# ImageProc_2_5.net
KiCad netlist of a schematic drawn in EAGLE
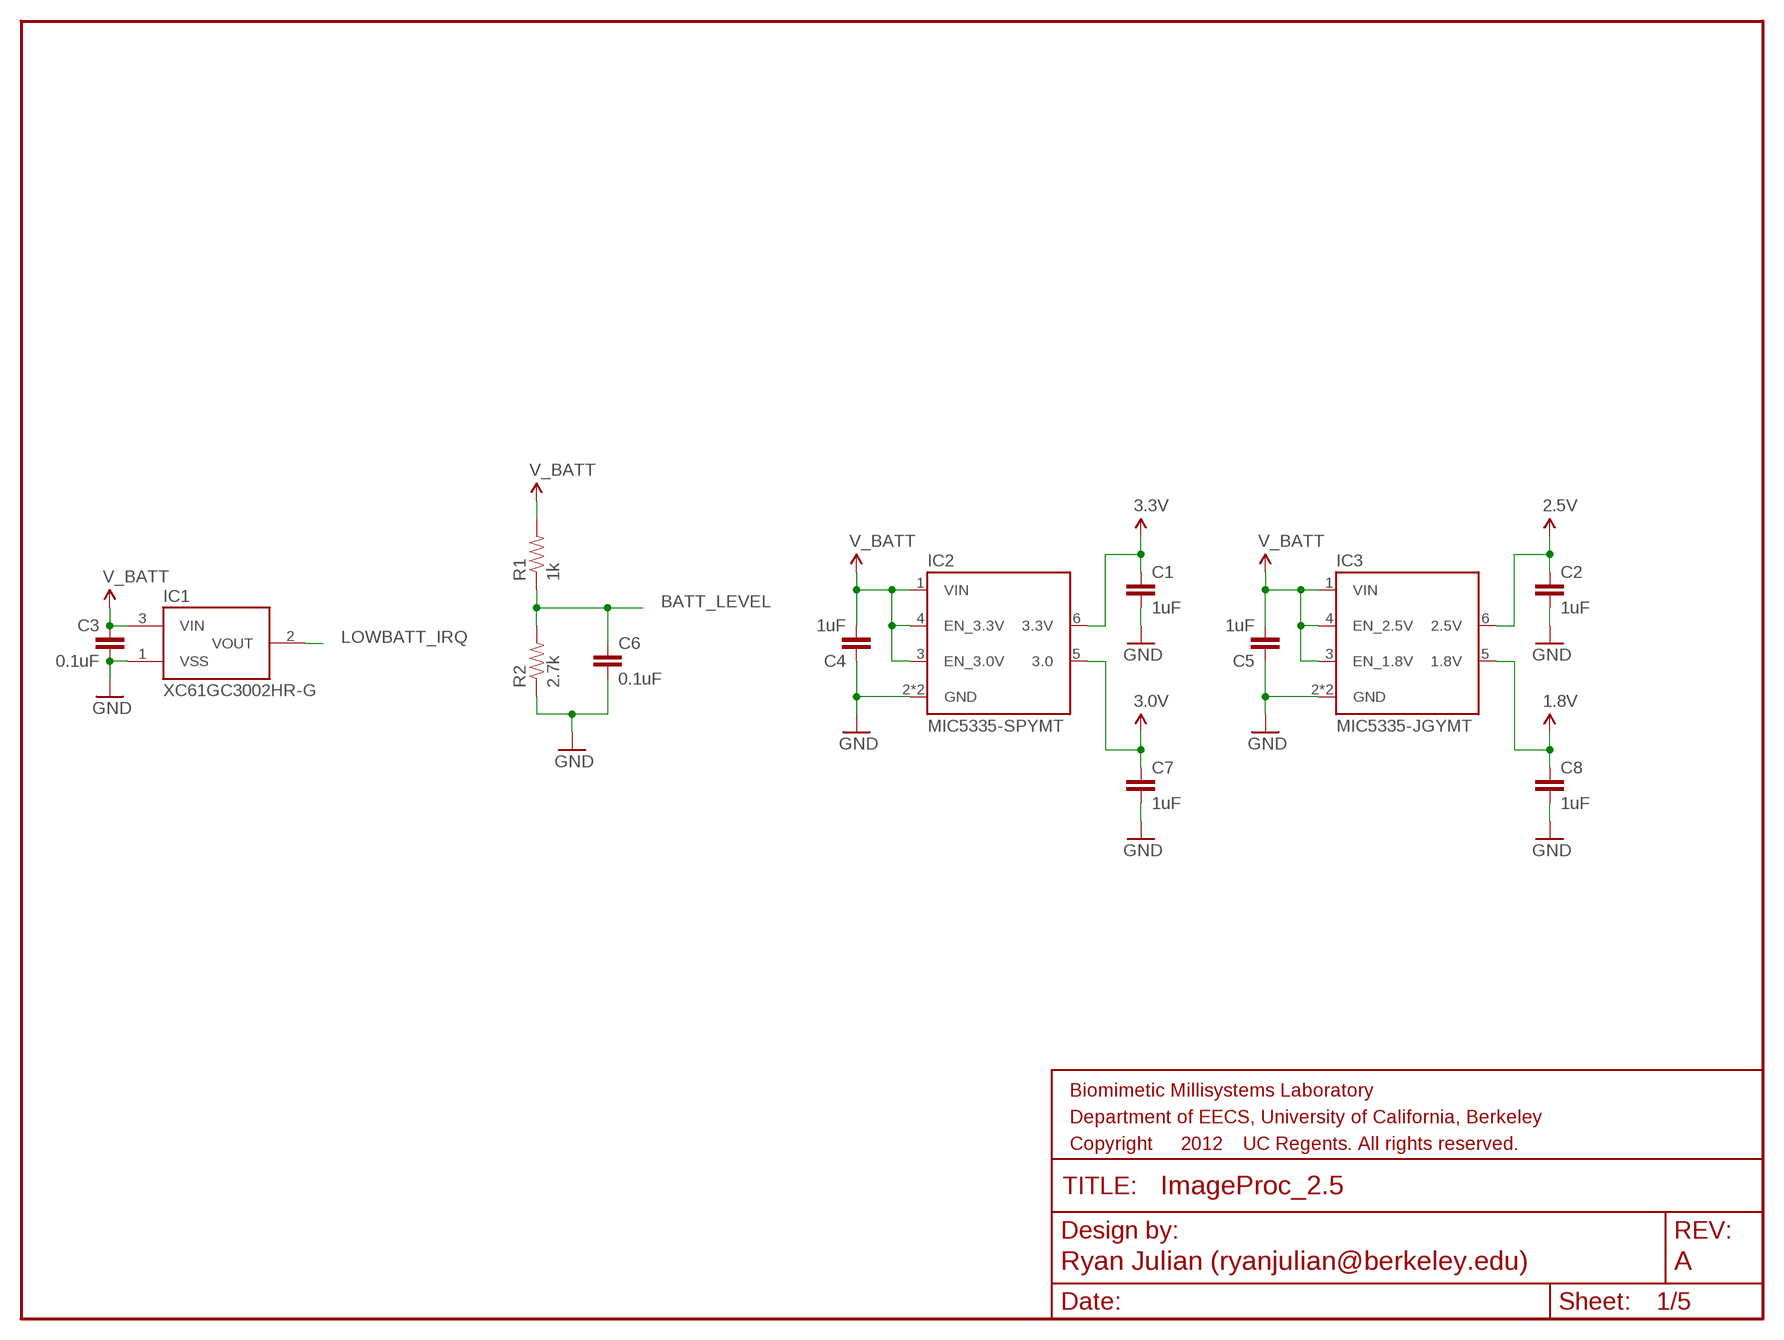
[diagram p0: schematic, sheet 1]
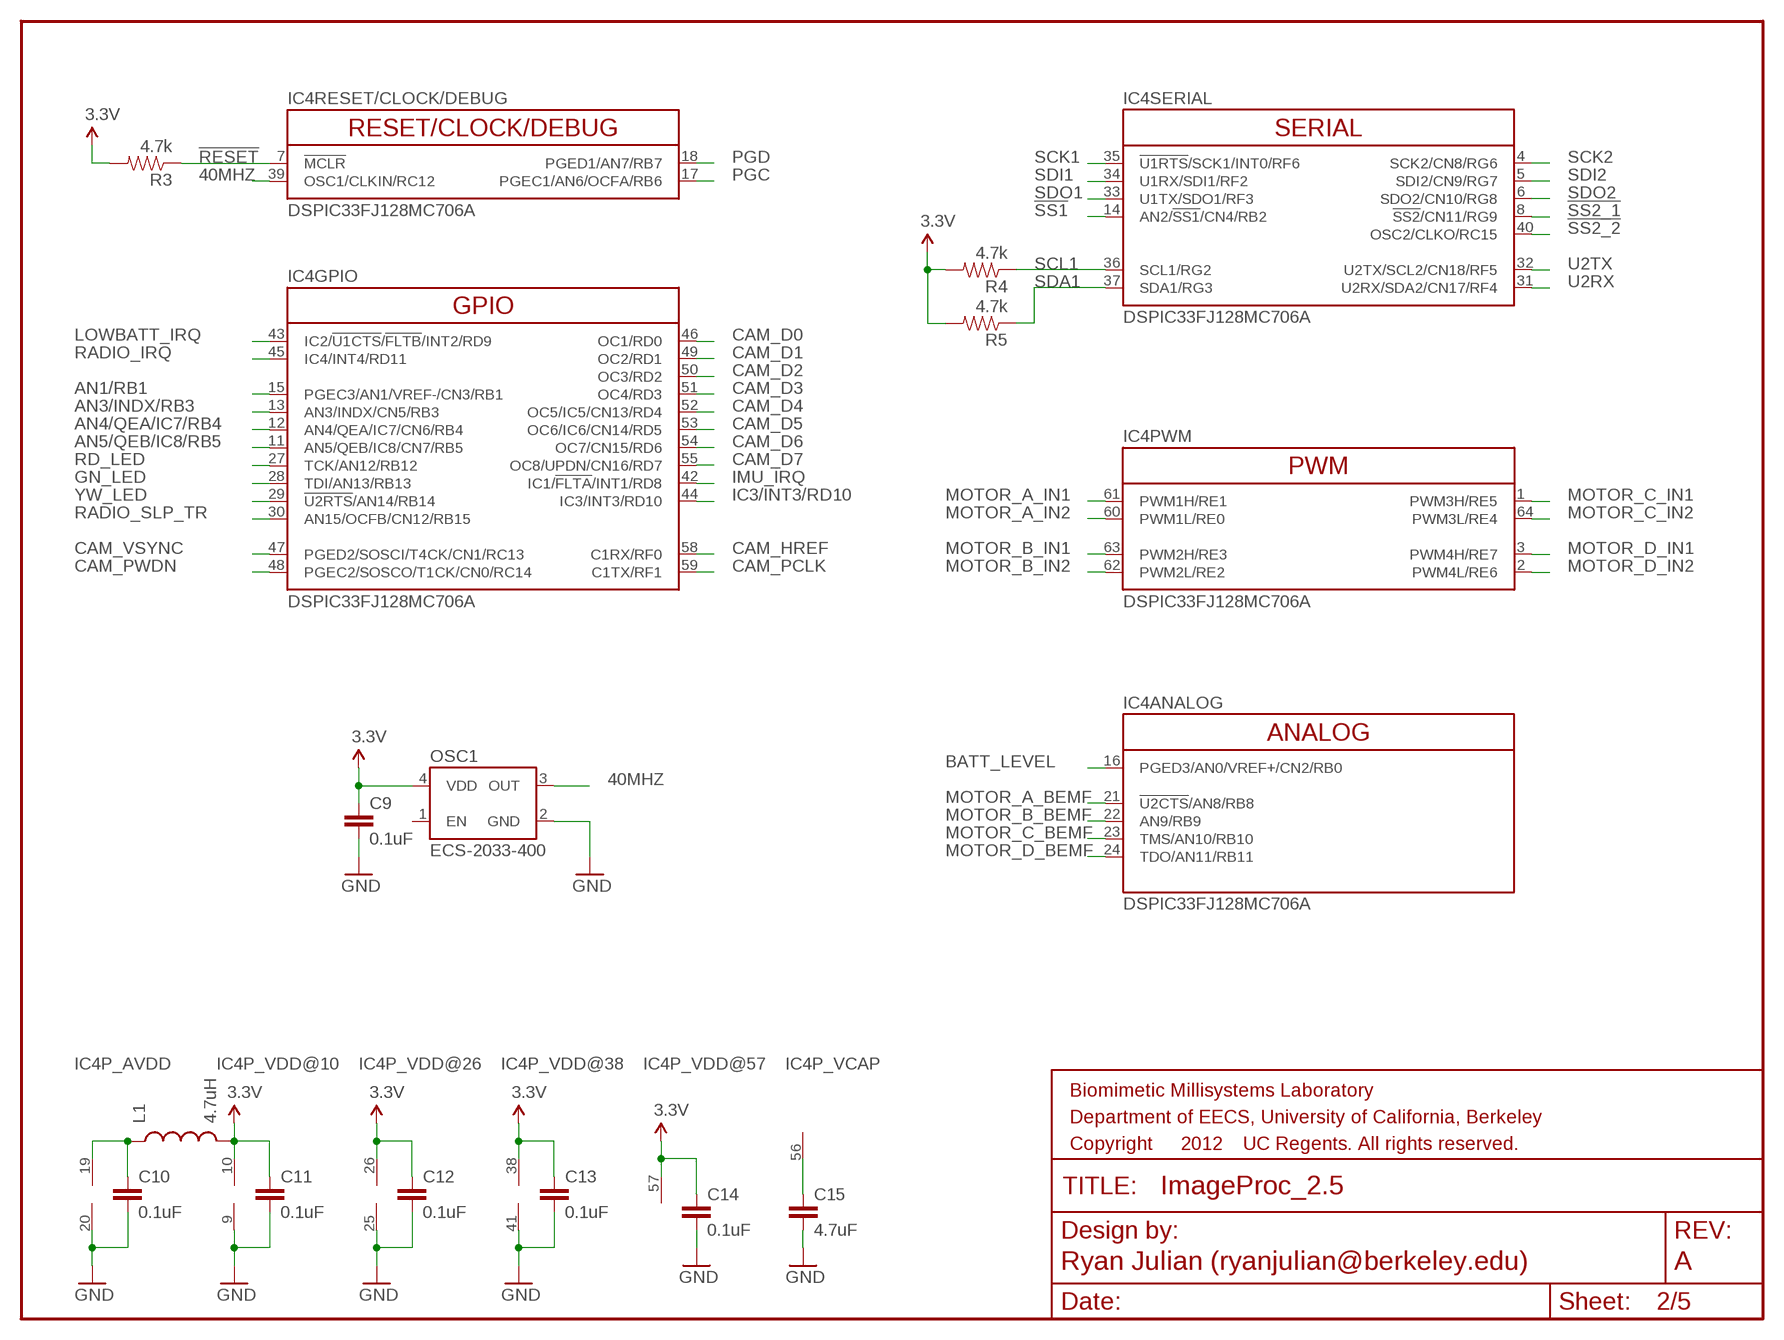
[diagram p1: schematic, sheet 2]
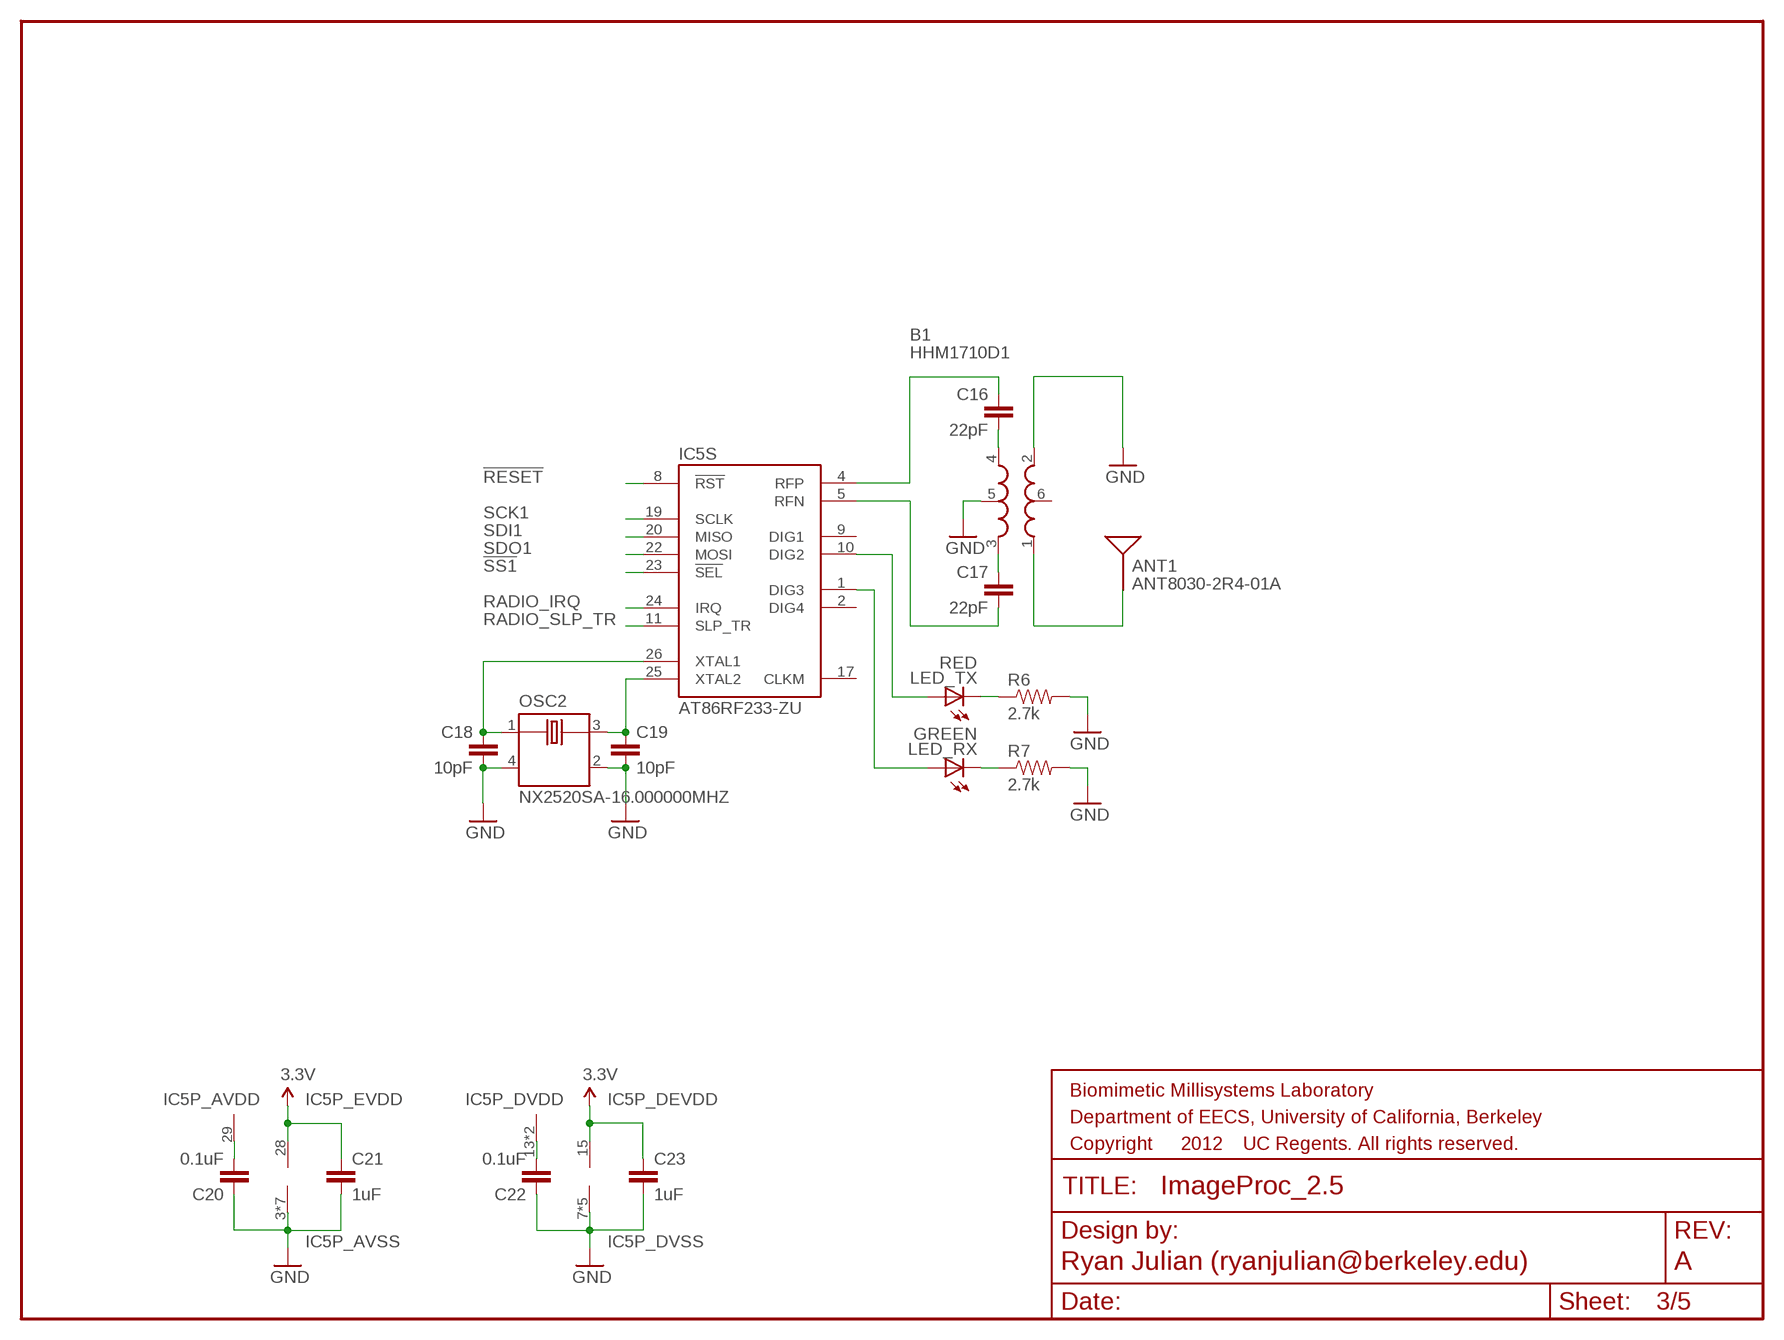
[diagram p2: schematic, sheet 3]
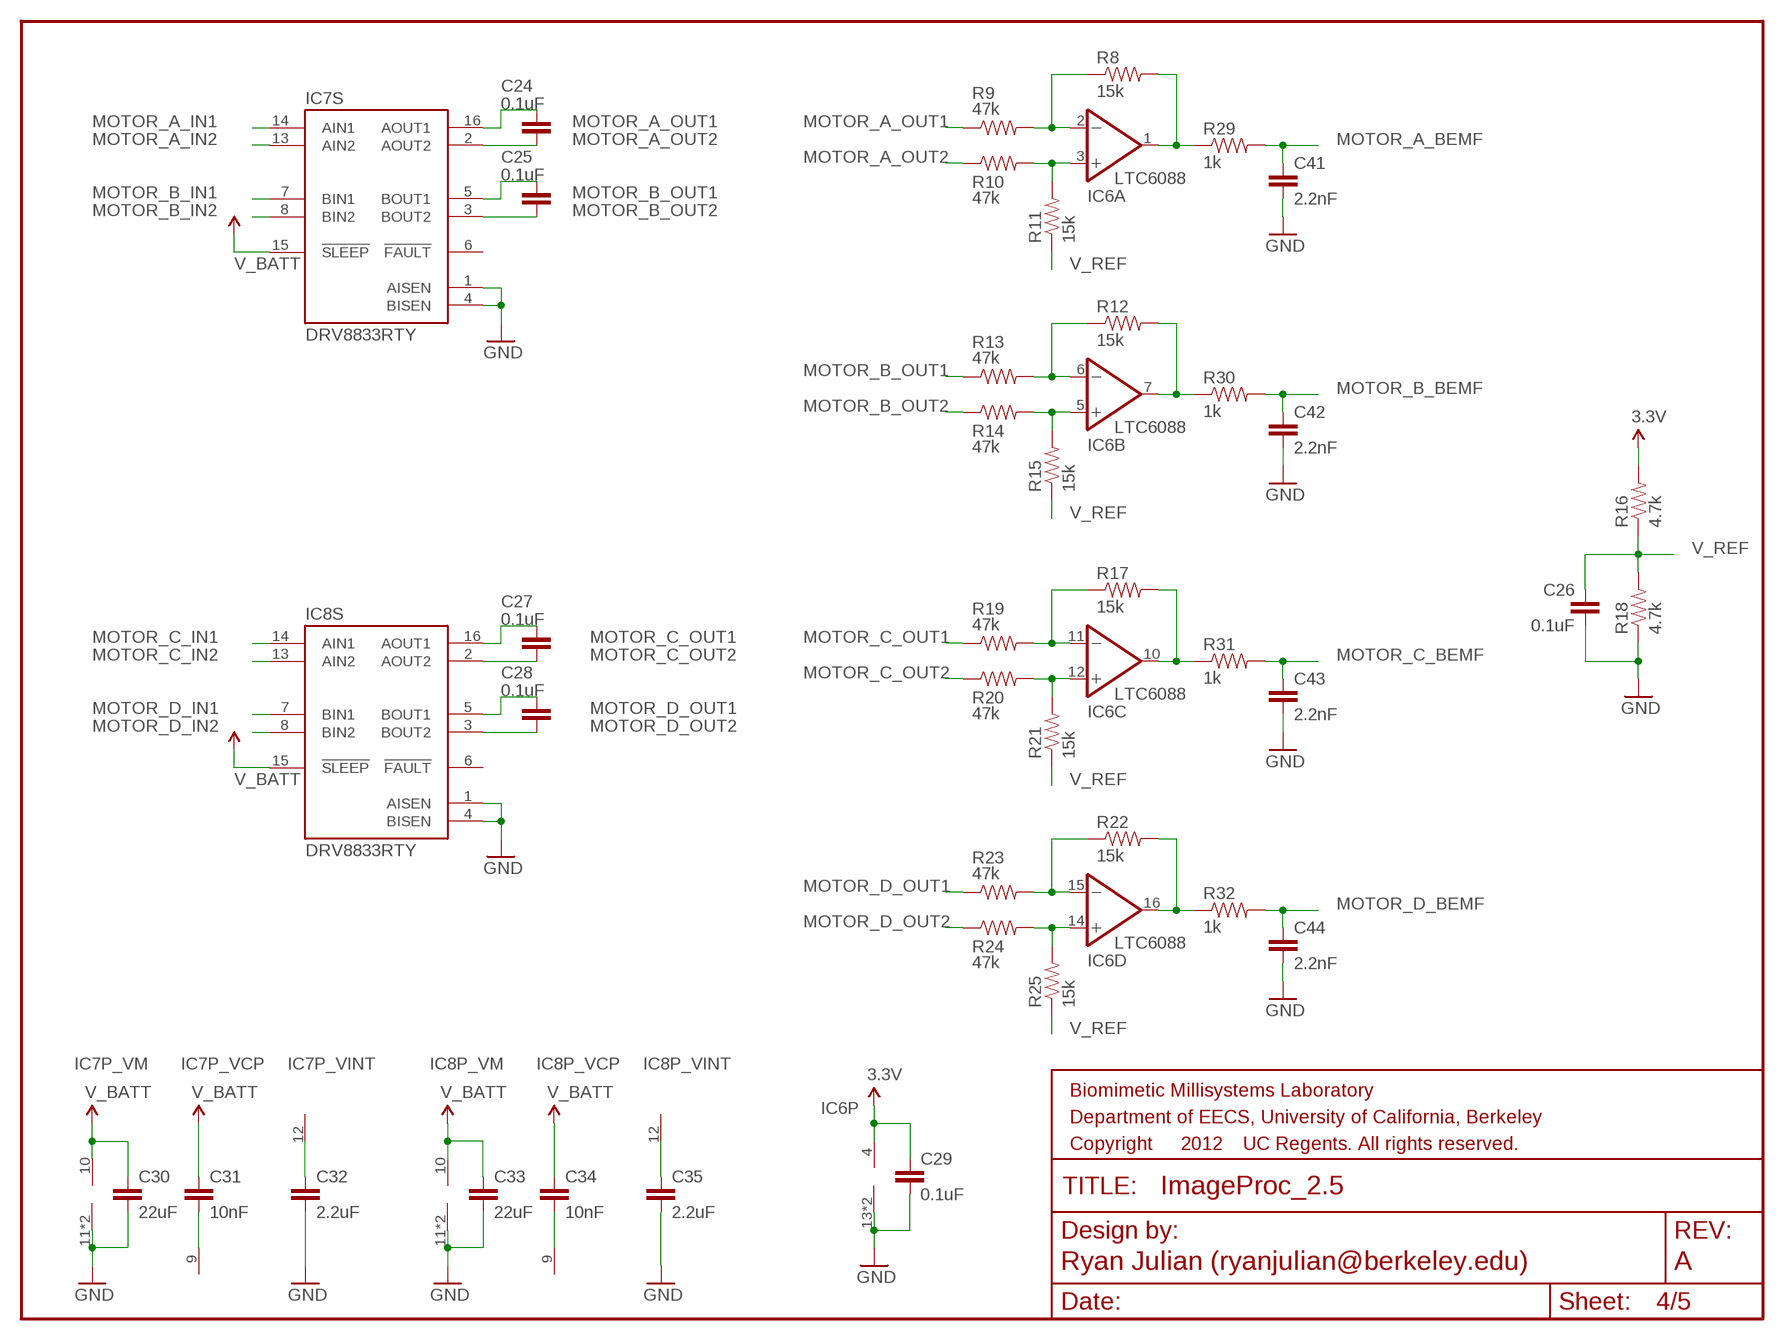
[diagram p3: schematic, sheet 4]
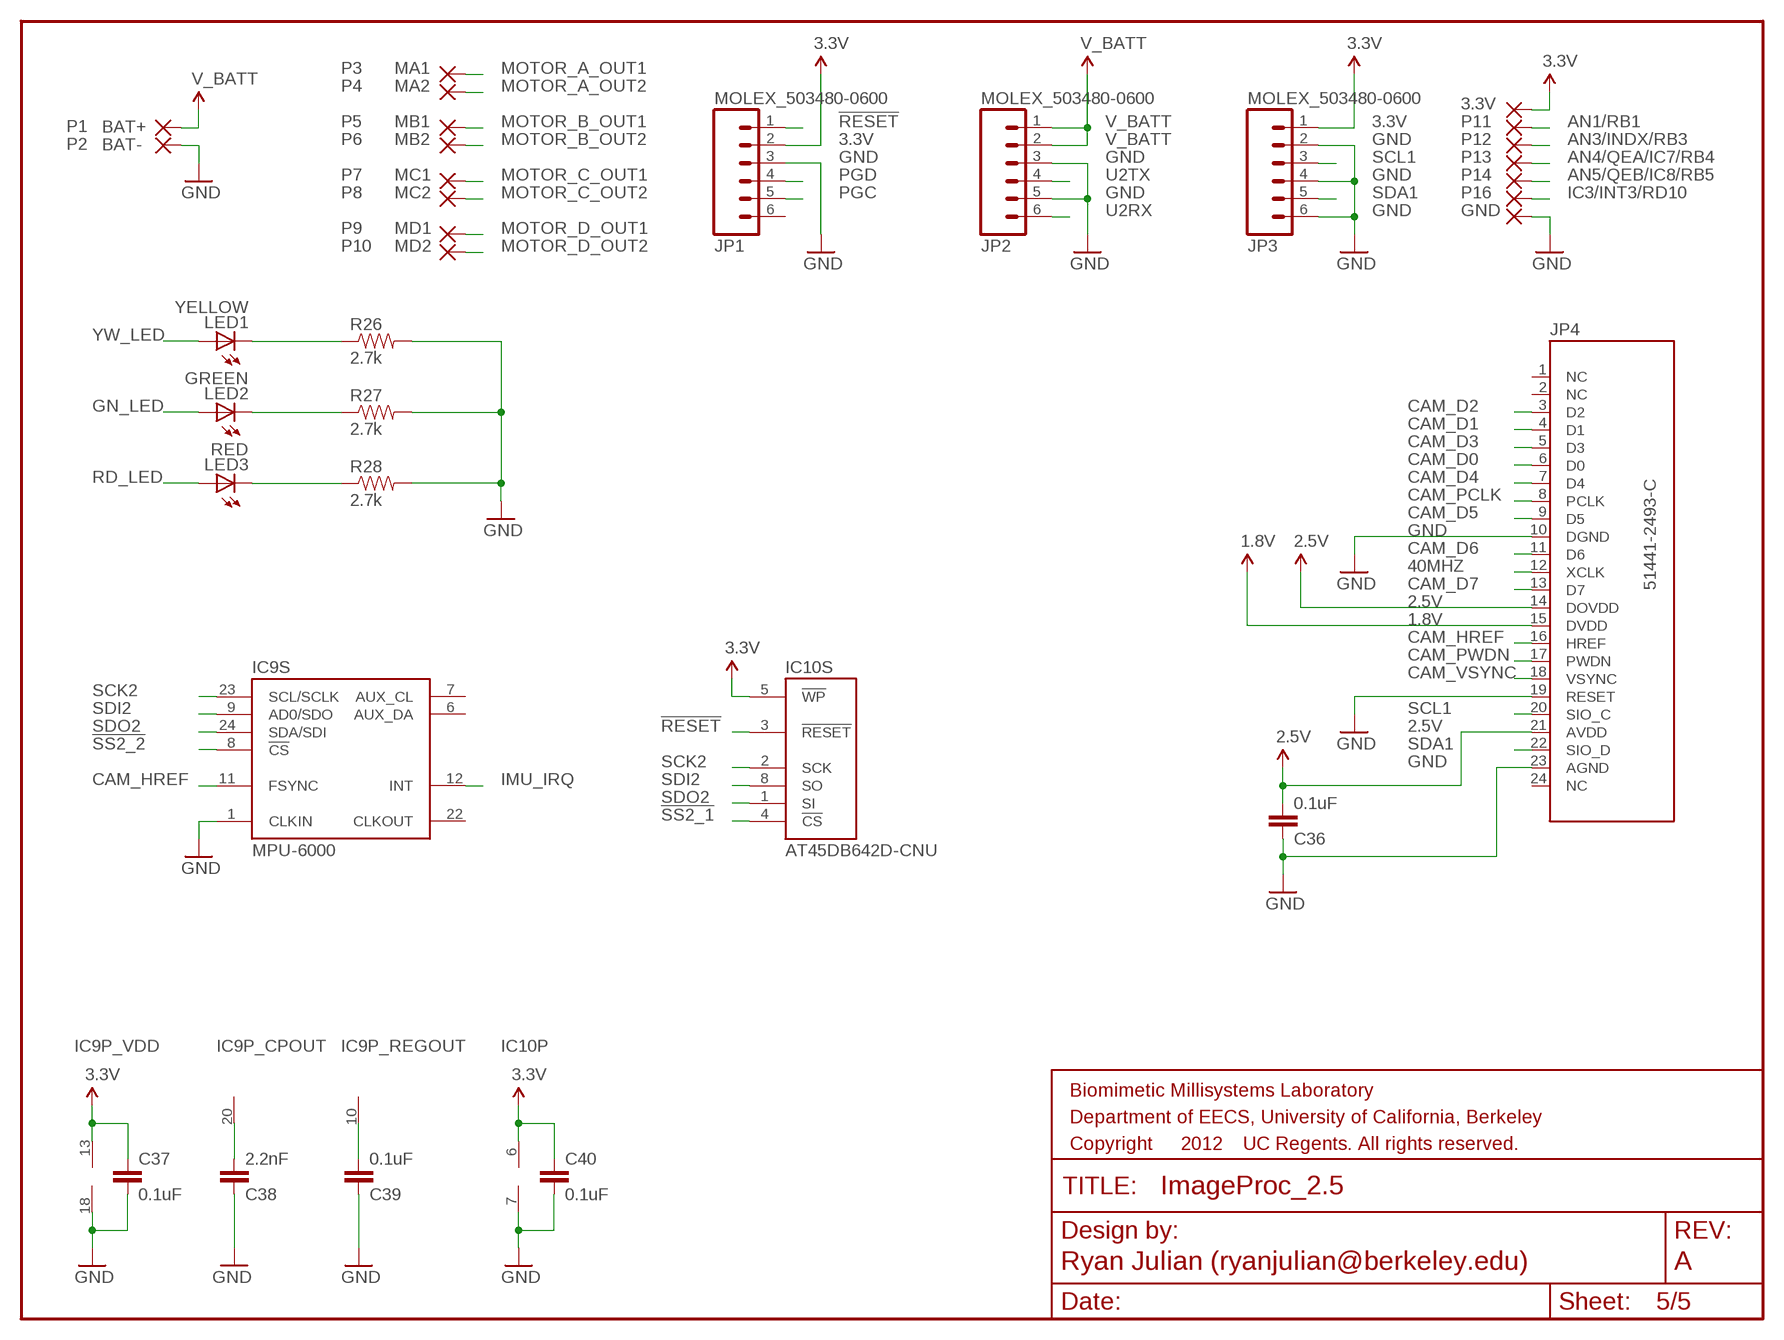
[diagram p4: schematic, sheet 5]

(export (version "E")
  (design (tool "Eeschema 10.0.6"))
  (components
    (comp (ref "C24")
      (value "0.1uF")
      (footprint "eagle-import:0402-CAP")
      (fields (field (name "VOLTAGE") "10V"))
      (libsource (lib "eagle-import") (part "CAP0402-CAP"))
    )
    (comp (ref "C25")
      (value "0.1uF")
      (footprint "eagle-import:0402-CAP")
      (fields (field (name "VOLTAGE") "10V"))
      (libsource (lib "eagle-import") (part "CAP0402-CAP"))
    )
    (comp (ref "C26")
      (value "0.1uF")
      (footprint "eagle-import:0402-CAP")
      (libsource (lib "eagle-import") (part "CAP0402-CAP"))
    )
    (comp (ref "C27")
      (value "0.1uF")
      (footprint "eagle-import:0402-CAP")
      (fields (field (name "VOLTAGE") "10V"))
      (libsource (lib "eagle-import") (part "CAP0402-CAP"))
    )
    (comp (ref "C28")
      (value "0.1uF")
      (footprint "eagle-import:0402-CAP")
      (fields (field (name "VOLTAGE") "10V"))
      (libsource (lib "eagle-import") (part "CAP0402-CAP"))
    )
    (comp (ref "C29")
      (value "0.1uF")
      (footprint "eagle-import:0402-CAP")
      (libsource (lib "eagle-import") (part "CAP0402-CAP"))
    )
    (comp (ref "C30")
      (value "22uF")
      (footprint "eagle-import:0603-CAP")
      (libsource (lib "eagle-import") (part "CAP0603-CAP"))
    )
    (comp (ref "C31")
      (value "10nF")
      (footprint "eagle-import:0402-CAP")
      (fields (field (name "VOLTAGE") "16V"))
      (libsource (lib "eagle-import") (part "CAP0402-CAP"))
    )
    (comp (ref "C32")
      (value "2.2uF")
      (footprint "eagle-import:0402-CAP")
      (fields (field (name "VOLTAGE") "6.3V"))
      (libsource (lib "eagle-import") (part "CAP0402-CAP"))
    )
    (comp (ref "C33")
      (value "22uF")
      (footprint "eagle-import:0603-CAP")
      (libsource (lib "eagle-import") (part "CAP0603-CAP"))
    )
    (comp (ref "C34")
      (value "10nF")
      (footprint "eagle-import:0402-CAP")
      (fields (field (name "VOLTAGE") "16V"))
      (libsource (lib "eagle-import") (part "CAP0402-CAP"))
    )
    (comp (ref "C35")
      (value "2.2uF")
      (footprint "eagle-import:0402-CAP")
      (fields (field (name "VOLTAGE") "6.3V"))
      (libsource (lib "eagle-import") (part "CAP0402-CAP"))
    )
    (comp (ref "C41")
      (value "2.2nF")
      (footprint "eagle-import:0402-CAP")
      (libsource (lib "eagle-import") (part "CAP0402-CAP"))
    )
    (comp (ref "C42")
      (value "2.2nF")
      (footprint "eagle-import:0402-CAP")
      (libsource (lib "eagle-import") (part "CAP0402-CAP"))
    )
    (comp (ref "C43")
      (value "2.2nF")
      (footprint "eagle-import:0402-CAP")
      (libsource (lib "eagle-import") (part "CAP0402-CAP"))
    )
    (comp (ref "C44")
      (value "2.2nF")
      (footprint "eagle-import:0402-CAP")
      (libsource (lib "eagle-import") (part "CAP0402-CAP"))
    )
    (comp (ref "IC6")
      (value "LTC6088")
      (footprint "eagle-import:DFN-16")
      (libsource (lib "eagle-import") (part "LTC6088"))
    )
    (comp (ref "IC7")
      (value "DRV8833RTY")
      (footprint "eagle-import:S-PWQFN-N16")
      (libsource (lib "eagle-import") (part "DRV8833RTY"))
    )
    (comp (ref "IC8")
      (value "DRV8833RTY")
      (footprint "eagle-import:S-PWQFN-N16")
      (libsource (lib "eagle-import") (part "DRV8833RTY"))
    )
    (comp (ref "R8")
      (value "15k")
      (footprint "eagle-import:0402-RES")
      (fields (field (name "TOLERANCE") "1%"))
      (libsource (lib "eagle-import") (part "RESISTOR0402-RES"))
    )
    (comp (ref "R9")
      (value "47k")
      (footprint "eagle-import:0402-RES")
      (fields (field (name "TOLERANCE") "1%"))
      (libsource (lib "eagle-import") (part "RESISTOR0402-RES"))
    )
    (comp (ref "R10")
      (value "47k")
      (footprint "eagle-import:0402-RES")
      (fields (field (name "TOLERANCE") "1%"))
      (libsource (lib "eagle-import") (part "RESISTOR0402-RES"))
    )
    (comp (ref "R11")
      (value "15k")
      (footprint "eagle-import:0402-RES")
      (fields (field (name "TOLERANCE") "1%"))
      (libsource (lib "eagle-import") (part "RESISTOR0402-RES"))
    )
    (comp (ref "R12")
      (value "15k")
      (footprint "eagle-import:0402-RES")
      (fields (field (name "TOLERANCE") "1%"))
      (libsource (lib "eagle-import") (part "RESISTOR0402-RES"))
    )
    (comp (ref "R13")
      (value "47k")
      (footprint "eagle-import:0402-RES")
      (fields (field (name "TOLERANCE") "1%"))
      (libsource (lib "eagle-import") (part "RESISTOR0402-RES"))
    )
    (comp (ref "R14")
      (value "47k")
      (footprint "eagle-import:0402-RES")
      (fields (field (name "TOLERANCE") "1%"))
      (libsource (lib "eagle-import") (part "RESISTOR0402-RES"))
    )
    (comp (ref "R15")
      (value "15k")
      (footprint "eagle-import:0402-RES")
      (fields (field (name "TOLERANCE") "1%"))
      (libsource (lib "eagle-import") (part "RESISTOR0402-RES"))
    )
    (comp (ref "R16")
      (value "4.7k")
      (footprint "eagle-import:0402-RES")
      (fields (field (name "TOLERANCE") "1%"))
      (libsource (lib "eagle-import") (part "RESISTOR0402-RES"))
    )
    (comp (ref "R17")
      (value "15k")
      (footprint "eagle-import:0402-RES")
      (fields (field (name "TOLERANCE") "1%"))
      (libsource (lib "eagle-import") (part "RESISTOR0402-RES"))
    )
    (comp (ref "R18")
      (value "4.7k")
      (footprint "eagle-import:0402-RES")
      (fields (field (name "TOLERANCE") "1%"))
      (libsource (lib "eagle-import") (part "RESISTOR0402-RES"))
    )
    (comp (ref "R19")
      (value "47k")
      (footprint "eagle-import:0402-RES")
      (fields (field (name "TOLERANCE") "1%"))
      (libsource (lib "eagle-import") (part "RESISTOR0402-RES"))
    )
    (comp (ref "R20")
      (value "47k")
      (footprint "eagle-import:0402-RES")
      (fields (field (name "TOLERANCE") "1%"))
      (libsource (lib "eagle-import") (part "RESISTOR0402-RES"))
    )
    (comp (ref "R21")
      (value "15k")
      (footprint "eagle-import:0402-RES")
      (fields (field (name "TOLERANCE") "1%"))
      (libsource (lib "eagle-import") (part "RESISTOR0402-RES"))
    )
    (comp (ref "R22")
      (value "15k")
      (footprint "eagle-import:0402-RES")
      (fields (field (name "TOLERANCE") "1%"))
      (libsource (lib "eagle-import") (part "RESISTOR0402-RES"))
    )
    (comp (ref "R23")
      (value "47k")
      (footprint "eagle-import:0402-RES")
      (fields (field (name "TOLERANCE") "1%"))
      (libsource (lib "eagle-import") (part "RESISTOR0402-RES"))
    )
    (comp (ref "R24")
      (value "47k")
      (footprint "eagle-import:0402-RES")
      (fields (field (name "TOLERANCE") "1%"))
      (libsource (lib "eagle-import") (part "RESISTOR0402-RES"))
    )
    (comp (ref "R25")
      (value "15k")
      (footprint "eagle-import:0402-RES")
      (fields (field (name "TOLERANCE") "1%"))
      (libsource (lib "eagle-import") (part "RESISTOR0402-RES"))
    )
    (comp (ref "R29")
      (value "1k")
      (footprint "eagle-import:0402-RES")
      (libsource (lib "eagle-import") (part "RESISTOR0402-RES"))
    )
    (comp (ref "R30")
      (value "1k")
      (footprint "eagle-import:0402-RES")
      (libsource (lib "eagle-import") (part "RESISTOR0402-RES"))
    )
    (comp (ref "R31")
      (value "1k")
      (footprint "eagle-import:0402-RES")
      (libsource (lib "eagle-import") (part "RESISTOR0402-RES"))
    )
    (comp (ref "R32")
      (value "1k")
      (footprint "eagle-import:0402-RES")
      (libsource (lib "eagle-import") (part "RESISTOR0402-RES"))
    )
    (comp (ref "C1")
      (value "1uF")
      (footprint "eagle-import:0402-CAP")
      (libsource (lib "eagle-import") (part "CAP0402-CAP"))
    )
    (comp (ref "C2")
      (value "1uF")
      (footprint "eagle-import:0402-CAP")
      (libsource (lib "eagle-import") (part "CAP0402-CAP"))
    )
    (comp (ref "C3")
      (value "0.1uF")
      (footprint "eagle-import:0402-CAP")
      (libsource (lib "eagle-import") (part "CAP0402-CAP"))
    )
    (comp (ref "C4")
      (value "1uF")
      (footprint "eagle-import:0402-CAP")
      (libsource (lib "eagle-import") (part "CAP0402-CAP"))
    )
    (comp (ref "C5")
      (value "1uF")
      (footprint "eagle-import:0402-CAP")
      (libsource (lib "eagle-import") (part "CAP0402-CAP"))
    )
    (comp (ref "C6")
      (value "0.1uF")
      (footprint "eagle-import:0402-CAP")
      (libsource (lib "eagle-import") (part "CAP0402-CAP"))
    )
    (comp (ref "C7")
      (value "1uF")
      (footprint "eagle-import:0402-CAP")
      (libsource (lib "eagle-import") (part "CAP0402-CAP"))
    )
    (comp (ref "C8")
      (value "1uF")
      (footprint "eagle-import:0402-CAP")
      (libsource (lib "eagle-import") (part "CAP0402-CAP"))
    )
    (comp (ref "IC1")
      (value "XC61GC3002HR-G")
      (footprint "eagle-import:USP-3")
      (libsource (lib "eagle-import") (part "XC61GC3002HR-G"))
    )
    (comp (ref "IC2")
      (value "MIC5335-SPYMT")
      (footprint "eagle-import:MLF-6")
      (libsource (lib "eagle-import") (part "MIC5335-SPYMT"))
    )
    (comp (ref "IC3")
      (value "MIC5335-JGYMT")
      (footprint "eagle-import:MLF-6")
      (libsource (lib "eagle-import") (part "MIC5335-JGYMT"))
    )
    (comp (ref "R1")
      (value "1k")
      (footprint "eagle-import:0402-RES")
      (libsource (lib "eagle-import") (part "RESISTOR0402-RES"))
    )
    (comp (ref "R2")
      (value "2.7k")
      (footprint "eagle-import:0402-RES")
      (libsource (lib "eagle-import") (part "RESISTOR0402-RES"))
    )
    (comp (ref "ANT1")
      (value "ANT8030-2R4-01A")
      (footprint "eagle-import:ANT8030-2R4-01A")
      (libsource (lib "eagle-import") (part "ANT8030-2R4-01A"))
    )
    (comp (ref "B1")
      (value "HHM1710D1")
      (footprint "eagle-import:0603-BALUN")
      (libsource (lib "eagle-import") (part "HHM1710D1"))
    )
    (comp (ref "C16")
      (value "22pF")
      (footprint "eagle-import:0402-CAP")
      (fields (field (name "TOLERANCE") "5%") (field (name "VOLTAGE") "50V"))
      (libsource (lib "eagle-import") (part "CAP0402-CAP"))
    )
    (comp (ref "C17")
      (value "22pF")
      (footprint "eagle-import:0402-CAP")
      (fields (field (name "TOLERANCE") "5%") (field (name "VOLTAGE") "50V"))
      (libsource (lib "eagle-import") (part "CAP0402-CAP"))
    )
    (comp (ref "C18")
      (value "10pF")
      (footprint "eagle-import:0402-CAP")
      (fields (field (name "TOLERANCE") "10%") (field (name "VOLTAGE") "50V"))
      (libsource (lib "eagle-import") (part "CAP0402-CAP"))
    )
    (comp (ref "C19")
      (value "10pF")
      (footprint "eagle-import:0402-CAP")
      (fields (field (name "TOLERANCE") "10%") (field (name "VOLTAGE") "50V"))
      (libsource (lib "eagle-import") (part "CAP0402-CAP"))
    )
    (comp (ref "C20")
      (value "0.1uF")
      (footprint "eagle-import:0402-CAP")
      (fields (field (name "TOLERANCE") "10%") (field (name "VOLTAGE") "16V"))
      (libsource (lib "eagle-import") (part "CAP0402-CAP"))
    )
    (comp (ref "C21")
      (value "1uF")
      (footprint "eagle-import:0402-CAP")
      (fields (field (name "TOLERANCE") "10%") (field (name "VOLTAGE") "16V"))
      (libsource (lib "eagle-import") (part "CAP0402-CAP"))
    )
    (comp (ref "C22")
      (value "0.1uF")
      (footprint "eagle-import:0402-CAP")
      (fields (field (name "TOLERANCE") "10%") (field (name "VOLTAGE") "16V"))
      (libsource (lib "eagle-import") (part "CAP0402-CAP"))
    )
    (comp (ref "C23")
      (value "1uF")
      (footprint "eagle-import:0402-CAP")
      (fields (field (name "TOLERANCE") "10%") (field (name "VOLTAGE") "16V"))
      (libsource (lib "eagle-import") (part "CAP0402-CAP"))
    )
    (comp (ref "IC5")
      (value "AT86RF233-ZU")
      (footprint "eagle-import:VQFN-32QN2")
      (libsource (lib "eagle-import") (part "AT86RF233-ZU"))
    )
    (comp (ref "LED_RX")
      (value "GREEN")
      (footprint "eagle-import:LED-0603")
      (libsource (lib "eagle-import") (part "LED0603"))
    )
    (comp (ref "LED_TX")
      (value "RED")
      (footprint "eagle-import:LED-0603")
      (libsource (lib "eagle-import") (part "LED0603"))
    )
    (comp (ref "OSC2")
      (value "NX2520SA-16.000000MHZ")
      (footprint "eagle-import:CRYSTAL-SMD")
      (libsource (lib "eagle-import") (part "NX2520SA-16.000000MHZ"))
    )
    (comp (ref "R6")
      (value "2.7k")
      (footprint "eagle-import:0402-RES")
      (libsource (lib "eagle-import") (part "RESISTOR0402-RES"))
    )
    (comp (ref "R7")
      (value "2.7k")
      (footprint "eagle-import:0402-RES")
      (libsource (lib "eagle-import") (part "RESISTOR0402-RES"))
    )
    (comp (ref "3.3V")
      (value "EXT5")
      (footprint "eagle-import:SMD1,27-2,54")
      (libsource (lib "eagle-import") (part "SMD2"))
    )
    (comp (ref "C36")
      (value "0.1uF")
      (footprint "eagle-import:0402-CAP")
      (libsource (lib "eagle-import") (part "CAP0402-CAP"))
    )
    (comp (ref "C37")
      (value "0.1uF")
      (footprint "eagle-import:0402-CAP")
      (fields (field (name "TOLERANCE") "10%") (field (name "VOLTAGE") "4V"))
      (libsource (lib "eagle-import") (part "CAP0402-CAP"))
    )
    (comp (ref "C38")
      (value "2.2nF")
      (footprint "eagle-import:0402-CAP")
      (fields (field (name "TOLERANCE") "10%") (field (name "VOLTAGE") "50V"))
      (libsource (lib "eagle-import") (part "CAP0402-CAP"))
    )
    (comp (ref "C39")
      (value "0.1uF")
      (footprint "eagle-import:0402-CAP")
      (fields (field (name "TOLERANCE") "10%") (field (name "VOLTAGE") "2V"))
      (libsource (lib "eagle-import") (part "CAP0402-CAP"))
    )
    (comp (ref "C40")
      (value "0.1uF")
      (footprint "eagle-import:0402-CAP")
      (libsource (lib "eagle-import") (part "CAP0402-CAP"))
    )
    (comp (ref "GND")
      (value "EXT5")
      (footprint "eagle-import:SMD1,27-2,54")
      (libsource (lib "eagle-import") (part "SMD2"))
    )
    (comp (ref "IC9")
      (value "MPU-6000")
      (footprint "eagle-import:QFN-24")
      (libsource (lib "eagle-import") (part "MPU-6000"))
    )
    (comp (ref "IC10")
      (value "AT45DB642D-CNU")
      (footprint "eagle-import:CASON-8")
      (libsource (lib "eagle-import") (part "AT45DB642D-CNU"))
    )
    (comp (ref "JP1")
      (value "MOLEX_503480-0600")
      (footprint "eagle-import:MOLEX_503480-0600")
      (libsource (lib "eagle-import") (part "MOLEX_503480-0600"))
    )
    (comp (ref "JP2")
      (value "MOLEX_503480-0600")
      (footprint "eagle-import:MOLEX_503480-0600")
      (libsource (lib "eagle-import") (part "MOLEX_503480-0600"))
    )
    (comp (ref "JP3")
      (value "MOLEX_503480-0600")
      (footprint "eagle-import:MOLEX_503480-0600")
      (libsource (lib "eagle-import") (part "MOLEX_503480-0600"))
    )
    (comp (ref "JP4")
      (value "51441-2493-C")
      (footprint "eagle-import:MOLEX_52740-2490")
      (libsource (lib "eagle-import") (part "OV7660FSL_CON"))
    )
    (comp (ref "LED1")
      (value "YELLOW")
      (footprint "eagle-import:LED-0603")
      (libsource (lib "eagle-import") (part "LED0603"))
    )
    (comp (ref "LED2")
      (value "GREEN")
      (footprint "eagle-import:LED-0603")
      (libsource (lib "eagle-import") (part "LED0603"))
    )
    (comp (ref "LED3")
      (value "RED")
      (footprint "eagle-import:LED-0603")
      (libsource (lib "eagle-import") (part "LED0603"))
    )
    (comp (ref "P1")
      (value "BAT+")
      (footprint "eagle-import:SMD1,27-2,54")
      (libsource (lib "eagle-import") (part "SMD2"))
    )
    (comp (ref "P2")
      (value "BAT-")
      (footprint "eagle-import:SMD1,27-2,54")
      (libsource (lib "eagle-import") (part "SMD2"))
    )
    (comp (ref "P3")
      (value "MA1")
      (footprint "eagle-import:SMD1,27-2,54")
      (libsource (lib "eagle-import") (part "SMD2"))
    )
    (comp (ref "P4")
      (value "MA2")
      (footprint "eagle-import:SMD1,27-2,54")
      (libsource (lib "eagle-import") (part "SMD2"))
    )
    (comp (ref "P5")
      (value "MB1")
      (footprint "eagle-import:SMD1,27-2,54")
      (libsource (lib "eagle-import") (part "SMD2"))
    )
    (comp (ref "P6")
      (value "MB2")
      (footprint "eagle-import:SMD1,27-2,54")
      (libsource (lib "eagle-import") (part "SMD2"))
    )
    (comp (ref "P7")
      (value "MC1")
      (footprint "eagle-import:SMD1,27-2,54")
      (libsource (lib "eagle-import") (part "SMD2"))
    )
    (comp (ref "P8")
      (value "MC2")
      (footprint "eagle-import:SMD1,27-2,54")
      (libsource (lib "eagle-import") (part "SMD2"))
    )
    (comp (ref "P9")
      (value "MD1")
      (footprint "eagle-import:SMD1,27-2,54")
      (libsource (lib "eagle-import") (part "SMD2"))
    )
    (comp (ref "P10")
      (value "MD2")
      (footprint "eagle-import:SMD1,27-2,54")
      (libsource (lib "eagle-import") (part "SMD2"))
    )
    (comp (ref "P11")
      (value "EXT1")
      (footprint "eagle-import:SMD1,27-2,54")
      (libsource (lib "eagle-import") (part "SMD2"))
    )
    (comp (ref "P12")
      (value "EXT2")
      (footprint "eagle-import:SMD1,27-2,54")
      (libsource (lib "eagle-import") (part "SMD2"))
    )
    (comp (ref "P13")
      (value "EXT3")
      (footprint "eagle-import:SMD1,27-2,54")
      (libsource (lib "eagle-import") (part "SMD2"))
    )
    (comp (ref "P14")
      (value "EXT4")
      (footprint "eagle-import:SMD1,27-2,54")
      (libsource (lib "eagle-import") (part "SMD2"))
    )
    (comp (ref "P16")
      (value "EXT5")
      (footprint "eagle-import:SMD1,27-2,54")
      (libsource (lib "eagle-import") (part "SMD2"))
    )
    (comp (ref "R26")
      (value "2.7k")
      (footprint "eagle-import:0402-RES")
      (libsource (lib "eagle-import") (part "RESISTOR0402-RES"))
    )
    (comp (ref "R27")
      (value "2.7k")
      (footprint "eagle-import:0402-RES")
      (libsource (lib "eagle-import") (part "RESISTOR0402-RES"))
    )
    (comp (ref "R28")
      (value "2.7k")
      (footprint "eagle-import:0402-RES")
      (libsource (lib "eagle-import") (part "RESISTOR0402-RES"))
    )
    (comp (ref "C9")
      (value "0.1uF")
      (footprint "eagle-import:0402-CAP")
      (libsource (lib "eagle-import") (part "CAP0402-CAP"))
    )
    (comp (ref "C10")
      (value "0.1uF")
      (footprint "eagle-import:0402-CAP")
      (libsource (lib "eagle-import") (part "CAP0402-CAP"))
    )
    (comp (ref "C11")
      (value "0.1uF")
      (footprint "eagle-import:0402-CAP")
      (libsource (lib "eagle-import") (part "CAP0402-CAP"))
    )
    (comp (ref "C12")
      (value "0.1uF")
      (footprint "eagle-import:0402-CAP")
      (libsource (lib "eagle-import") (part "CAP0402-CAP"))
    )
    (comp (ref "C13")
      (value "0.1uF")
      (footprint "eagle-import:0402-CAP")
      (libsource (lib "eagle-import") (part "CAP0402-CAP"))
    )
    (comp (ref "C14")
      (value "0.1uF")
      (footprint "eagle-import:0402-CAP")
      (libsource (lib "eagle-import") (part "CAP0402-CAP"))
    )
    (comp (ref "C15")
      (value "4.7uF")
      (footprint "eagle-import:0603-CAP")
      (fields (field (name "COMMENT") "ESR < 5 Ohm") (field (name "VOLTAGE") "16V"))
      (libsource (lib "eagle-import") (part "CAP0603-CAP"))
    )
    (comp (ref "IC4")
      (value "DSPIC33FJ128MC706A")
      (footprint "eagle-import:TQFP-64")
      (libsource (lib "eagle-import") (part "DSPIC33FJ128MC706A"))
    )
    (comp (ref "L1")
      (value "4.7uH")
      (footprint "eagle-import:0603")
      (libsource (lib "eagle-import") (part "INDUCTOR0603"))
    )
    (comp (ref "OSC1")
      (value "ECS-2033-400")
      (footprint "eagle-import:OSCILLATOR-SMD")
      (libsource (lib "eagle-import") (part "ECS-2033-400"))
    )
    (comp (ref "R3")
      (value "4.7k")
      (footprint "eagle-import:0402-RES")
      (libsource (lib "eagle-import") (part "RESISTOR0402-RES"))
    )
    (comp (ref "R4")
      (value "4.7k")
      (footprint "eagle-import:0402-RES")
      (libsource (lib "eagle-import") (part "RESISTOR0402-RES"))
    )
    (comp (ref "R5")
      (value "4.7k")
      (footprint "eagle-import:0402-RES")
      (libsource (lib "eagle-import") (part "RESISTOR0402-RES"))
    )
  )
  (nets
    (net (code "1") (name "1.8V") (class "Default")
      (node (ref "C8") (pin "1") (pinfunction "1_1") (pintype "passive"))
      (node (ref "IC3") (pin "5") (pinfunction "1.8V_5") (pintype "bidirectional"))
      (node (ref "JP4") (pin "15") (pinfunction "DVDD_15") (pintype "bidirectional"))
    )
    (net (code "2") (name "2.5V") (class "Default")
      (node (ref "C2") (pin "1") (pinfunction "1_1") (pintype "passive"))
      (node (ref "C36") (pin "2") (pinfunction "2_2") (pintype "passive"))
      (node (ref "IC3") (pin "6") (pinfunction "2.5V_6") (pintype "bidirectional"))
      (node (ref "JP4") (pin "14") (pinfunction "DOVDD_14") (pintype "bidirectional"))
      (node (ref "JP4") (pin "21") (pinfunction "AVDD_21") (pintype "bidirectional"))
    )
    (net (code "3") (name "3.0V") (class "Default")
      (node (ref "C7") (pin "1") (pinfunction "1_1") (pintype "passive"))
      (node (ref "IC2") (pin "5") (pinfunction "3.0_5") (pintype "bidirectional"))
    )
    (net (code "4") (name "3.3V") (class "Default")
      (node (ref "3.3V") (pin "1") (pinfunction "P_1") (pintype "passive"))
      (node (ref "C1") (pin "1") (pinfunction "1_1") (pintype "passive"))
      (node (ref "C11") (pin "1") (pinfunction "1_1") (pintype "passive"))
      (node (ref "C12") (pin "1") (pinfunction "1_1") (pintype "passive"))
      (node (ref "C13") (pin "1") (pinfunction "1_1") (pintype "passive"))
      (node (ref "C14") (pin "1") (pinfunction "1_1") (pintype "passive"))
      (node (ref "C21") (pin "1") (pinfunction "1_1") (pintype "passive"))
      (node (ref "C23") (pin "1") (pinfunction "1_1") (pintype "passive"))
      (node (ref "C29") (pin "1") (pinfunction "1_1") (pintype "passive"))
      (node (ref "C37") (pin "1") (pinfunction "1_1") (pintype "passive"))
      (node (ref "C40") (pin "1") (pinfunction "1_1") (pintype "passive"))
      (node (ref "C9") (pin "1") (pinfunction "1_1") (pintype "passive"))
      (node (ref "IC10") (pin "5") (pinfunction "~{WP}_5") (pintype "bidirectional"))
      (node (ref "IC10") (pin "6") (pinfunction "V+_6") (pintype "power_in"))
      (node (ref "IC2") (pin "6") (pinfunction "3.3V_6") (pintype "bidirectional"))
      (node (ref "IC4") (pin "10") (pinfunction "V+_10") (pintype "power_in"))
      (node (ref "IC4") (pin "26") (pinfunction "V+_26") (pintype "power_in"))
      (node (ref "IC4") (pin "38") (pinfunction "V+_38") (pintype "power_in"))
      (node (ref "IC4") (pin "57") (pinfunction "V+_57") (pintype "power_in"))
      (node (ref "IC5") (pin "15") (pinfunction "V+_15") (pintype "power_in"))
      (node (ref "IC5") (pin "28") (pinfunction "V+_28") (pintype "power_in"))
      (node (ref "IC6") (pin "4") (pinfunction "V+_4") (pintype "power_in"))
      (node (ref "IC9") (pin "13") (pinfunction "V+_13") (pintype "power_in"))
      (node (ref "JP1") (pin "2") (pinfunction "2_2") (pintype "passive"))
      (node (ref "JP3") (pin "1") (pinfunction "1_1") (pintype "passive"))
      (node (ref "L1") (pin "2") (pinfunction "2_2") (pintype "passive"))
      (node (ref "OSC1") (pin "4") (pinfunction "VDD_4") (pintype "bidirectional"))
      (node (ref "R16") (pin "2") (pinfunction "2_2") (pintype "passive"))
      (node (ref "R3") (pin "2") (pinfunction "2_2") (pintype "passive"))
      (node (ref "R4") (pin "2") (pinfunction "2_2") (pintype "passive"))
      (node (ref "R5") (pin "2") (pinfunction "2_2") (pintype "passive"))
    )
    (net (code "5") (name "40MHZ") (class "Default")
      (node (ref "IC4") (pin "39") (pinfunction "OSC1/CLKIN/RC12_39") (pintype "bidirectional"))
      (node (ref "JP4") (pin "12") (pinfunction "XCLK_12") (pintype "bidirectional"))
      (node (ref "OSC1") (pin "3") (pinfunction "OUT_3") (pintype "bidirectional"))
    )
    (net (code "6") (name "AN1{slash}RB1") (class "Default")
      (node (ref "IC4") (pin "15") (pinfunction "PGEC3/AN1/VREF-/CN3/RB1_15") (pintype "bidirectional"))
      (node (ref "P11") (pin "1") (pinfunction "P_1") (pintype "passive"))
    )
    (net (code "7") (name "AN3{slash}INDX{slash}RB3") (class "Default")
      (node (ref "IC4") (pin "13") (pinfunction "AN3/INDX/CN5/RB3_13") (pintype "bidirectional"))
      (node (ref "P12") (pin "1") (pinfunction "P_1") (pintype "passive"))
    )
    (net (code "8") (name "AN4{slash}QEA{slash}IC7{slash}RB4") (class "Default")
      (node (ref "IC4") (pin "12") (pinfunction "AN4/QEA/IC7/CN6/RB4_12") (pintype "bidirectional"))
      (node (ref "P13") (pin "1") (pinfunction "P_1") (pintype "passive"))
    )
    (net (code "9") (name "AN5{slash}QEB{slash}IC8{slash}RB5") (class "Default")
      (node (ref "IC4") (pin "11") (pinfunction "AN5/QEB/IC8/CN7/RB5_11") (pintype "bidirectional"))
      (node (ref "P14") (pin "1") (pinfunction "P_1") (pintype "passive"))
    )
    (net (code "10") (name "BATT_LEVEL") (class "Default")
      (node (ref "C6") (pin "1") (pinfunction "1_1") (pintype "passive"))
      (node (ref "IC4") (pin "16") (pinfunction "PGED3/AN0/VREF+/CN2/RB0_16") (pintype "bidirectional"))
      (node (ref "R1") (pin "1") (pinfunction "1_1") (pintype "passive"))
      (node (ref "R2") (pin "2") (pinfunction "2_2") (pintype "passive"))
    )
    (net (code "11") (name "CAM_D0") (class "Default")
      (node (ref "IC4") (pin "46") (pinfunction "OC1/RD0_46") (pintype "bidirectional"))
      (node (ref "JP4") (pin "6") (pinfunction "D0_6") (pintype "bidirectional"))
    )
    (net (code "12") (name "CAM_D1") (class "Default")
      (node (ref "IC4") (pin "49") (pinfunction "OC2/RD1_49") (pintype "bidirectional"))
      (node (ref "JP4") (pin "4") (pinfunction "D1_4") (pintype "bidirectional"))
    )
    (net (code "13") (name "CAM_D2") (class "Default")
      (node (ref "IC4") (pin "50") (pinfunction "OC3/RD2_50") (pintype "bidirectional"))
      (node (ref "JP4") (pin "3") (pinfunction "D2_3") (pintype "bidirectional"))
    )
    (net (code "14") (name "CAM_D3") (class "Default")
      (node (ref "IC4") (pin "51") (pinfunction "OC4/RD3_51") (pintype "bidirectional"))
      (node (ref "JP4") (pin "5") (pinfunction "D3_5") (pintype "bidirectional"))
    )
    (net (code "15") (name "CAM_D4") (class "Default")
      (node (ref "IC4") (pin "52") (pinfunction "OC5/IC5/CN13/RD4_52") (pintype "bidirectional"))
      (node (ref "JP4") (pin "7") (pinfunction "D4_7") (pintype "bidirectional"))
    )
    (net (code "16") (name "CAM_D5") (class "Default")
      (node (ref "IC4") (pin "53") (pinfunction "OC6/IC6/CN14/RD5_53") (pintype "bidirectional"))
      (node (ref "JP4") (pin "9") (pinfunction "D5_9") (pintype "bidirectional"))
    )
    (net (code "17") (name "CAM_D6") (class "Default")
      (node (ref "IC4") (pin "54") (pinfunction "OC7/CN15/RD6_54") (pintype "bidirectional"))
      (node (ref "JP4") (pin "11") (pinfunction "D6_11") (pintype "bidirectional"))
    )
    (net (code "18") (name "CAM_D7") (class "Default")
      (node (ref "IC4") (pin "55") (pinfunction "OC8/UPDN/CN16/RD7_55") (pintype "bidirectional"))
      (node (ref "JP4") (pin "13") (pinfunction "D7_13") (pintype "bidirectional"))
    )
    (net (code "19") (name "CAM_HREF") (class "Default")
      (node (ref "IC4") (pin "58") (pinfunction "C1RX/RF0_58") (pintype "bidirectional"))
      (node (ref "IC9") (pin "11") (pinfunction "FSYNC_11") (pintype "bidirectional"))
      (node (ref "JP4") (pin "16") (pinfunction "HREF_16") (pintype "bidirectional"))
    )
    (net (code "20") (name "CAM_PCLK") (class "Default")
      (node (ref "IC4") (pin "59") (pinfunction "C1TX/RF1_59") (pintype "bidirectional"))
      (node (ref "JP4") (pin "8") (pinfunction "PCLK_8") (pintype "bidirectional"))
    )
    (net (code "21") (name "CAM_PWDN") (class "Default")
      (node (ref "IC4") (pin "48") (pinfunction "PGEC2/SOSCO/T1CK/CN0/RC14_48") (pintype "bidirectional"))
      (node (ref "JP4") (pin "17") (pinfunction "PWDN_17") (pintype "bidirectional"))
    )
    (net (code "22") (name "CAM_VSYNC") (class "Default")
      (node (ref "IC4") (pin "47") (pinfunction "PGED2/SOSCI/T4CK/CN1/RC13_47") (pintype "bidirectional"))
      (node (ref "JP4") (pin "18") (pinfunction "VSYNC_18") (pintype "bidirectional"))
    )
    (net (code "23") (name "GND") (class "Default")
      (node (ref "B1") (pin "2") (pinfunction "RFGND_2") (pintype "bidirectional"))
      (node (ref "B1") (pin "5") (pinfunction "GND_5") (pintype "bidirectional"))
      (node (ref "C1") (pin "2") (pinfunction "2_2") (pintype "passive"))
      (node (ref "C10") (pin "2") (pinfunction "2_2") (pintype "passive"))
      (node (ref "C11") (pin "2") (pinfunction "2_2") (pintype "passive"))
      (node (ref "C12") (pin "2") (pinfunction "2_2") (pintype "passive"))
      (node (ref "C13") (pin "2") (pinfunction "2_2") (pintype "passive"))
      (node (ref "C14") (pin "2") (pinfunction "2_2") (pintype "passive"))
      (node (ref "C15") (pin "2") (pinfunction "2_2") (pintype "passive"))
      (node (ref "C18") (pin "2") (pinfunction "2_2") (pintype "passive"))
      (node (ref "C19") (pin "2") (pinfunction "2_2") (pintype "passive"))
      (node (ref "C2") (pin "2") (pinfunction "2_2") (pintype "passive"))
      (node (ref "C20") (pin "1") (pinfunction "1_1") (pintype "passive"))
      (node (ref "C21") (pin "2") (pinfunction "2_2") (pintype "passive"))
      (node (ref "C22") (pin "1") (pinfunction "1_1") (pintype "passive"))
      (node (ref "C23") (pin "2") (pinfunction "2_2") (pintype "passive"))
      (node (ref "C26") (pin "2") (pinfunction "2_2") (pintype "passive"))
      (node (ref "C29") (pin "2") (pinfunction "2_2") (pintype "passive"))
      (node (ref "C3") (pin "2") (pinfunction "2_2") (pintype "passive"))
      (node (ref "C30") (pin "2") (pinfunction "2_2") (pintype "passive"))
      (node (ref "C32") (pin "2") (pinfunction "2_2") (pintype "passive"))
      (node (ref "C33") (pin "2") (pinfunction "2_2") (pintype "passive"))
      (node (ref "C35") (pin "2") (pinfunction "2_2") (pintype "passive"))
      (node (ref "C36") (pin "1") (pinfunction "1_1") (pintype "passive"))
      (node (ref "C37") (pin "2") (pinfunction "2_2") (pintype "passive"))
      (node (ref "C38") (pin "1") (pinfunction "1_1") (pintype "passive"))
      (node (ref "C39") (pin "1") (pinfunction "1_1") (pintype "passive"))
      (node (ref "C4") (pin "1") (pinfunction "1_1") (pintype "passive"))
      (node (ref "C40") (pin "2") (pinfunction "2_2") (pintype "passive"))
      (node (ref "C41") (pin "2") (pinfunction "2_2") (pintype "passive"))
      (node (ref "C42") (pin "2") (pinfunction "2_2") (pintype "passive"))
      (node (ref "C43") (pin "2") (pinfunction "2_2") (pintype "passive"))
      (node (ref "C44") (pin "2") (pinfunction "2_2") (pintype "passive"))
      (node (ref "C5") (pin "1") (pinfunction "1_1") (pintype "passive"))
      (node (ref "C6") (pin "2") (pinfunction "2_2") (pintype "passive"))
      (node (ref "C7") (pin "2") (pinfunction "2_2") (pintype "passive"))
      (node (ref "C8") (pin "2") (pinfunction "2_2") (pintype "passive"))
      (node (ref "C9") (pin "2") (pinfunction "2_2") (pintype "passive"))
      (node (ref "GND") (pin "1") (pinfunction "P_1") (pintype "passive"))
      (node (ref "IC1") (pin "1") (pinfunction "VSS_1") (pintype "bidirectional"))
      (node (ref "IC10") (pin "7") (pinfunction "V-_7") (pintype "power_in"))
      (node (ref "IC2") (pin "2") (pinfunction "GND_2") (pintype "bidirectional"))
      (node (ref "IC2") (pin "EPAD") (pinfunction "GND_EPAD") (pintype "bidirectional"))
      (node (ref "IC3") (pin "2") (pinfunction "GND_2") (pintype "bidirectional"))
      (node (ref "IC3") (pin "EPAD") (pinfunction "GND_EPAD") (pintype "bidirectional"))
      (node (ref "IC4") (pin "20") (pinfunction "V-_20") (pintype "power_in"))
      (node (ref "IC4") (pin "25") (pinfunction "V-_25") (pintype "power_in"))
      (node (ref "IC4") (pin "41") (pinfunction "V-_41") (pintype "power_in"))
      (node (ref "IC4") (pin "9") (pinfunction "V-_9") (pintype "power_in"))
      (node (ref "IC5") (pin "12") (pinfunction "V-_12") (pintype "power_in"))
      (node (ref "IC5") (pin "16") (pinfunction "V-_16") (pintype "power_in"))
      (node (ref "IC5") (pin "18") (pinfunction "V-_18") (pintype "power_in"))
      (node (ref "IC5") (pin "21") (pinfunction "V-_21") (pintype "power_in"))
      (node (ref "IC5") (pin "27") (pinfunction "V-_27") (pintype "power_in"))
      (node (ref "IC5") (pin "3") (pinfunction "V-_3") (pintype "power_in"))
      (node (ref "IC5") (pin "30") (pinfunction "V-_30") (pintype "power_in"))
      (node (ref "IC5") (pin "31") (pinfunction "V-_31") (pintype "power_in"))
      (node (ref "IC5") (pin "32") (pinfunction "V-_32") (pintype "power_in"))
      (node (ref "IC5") (pin "6") (pinfunction "V-_6") (pintype "power_in"))
      (node (ref "IC5") (pin "7") (pinfunction "V-_7") (pintype "power_in"))
      (node (ref "IC5") (pin "PAD") (pinfunction "V-_PAD") (pintype "power_in"))
      (node (ref "IC6") (pin "13") (pinfunction "V-_13") (pintype "power_in"))
      (node (ref "IC6") (pin "PAD") (pinfunction "V-_PAD") (pintype "power_in"))
      (node (ref "IC7") (pin "1") (pinfunction "AISEN_1") (pintype "bidirectional"))
      (node (ref "IC7") (pin "11") (pinfunction "V-_11") (pintype "power_in"))
      (node (ref "IC7") (pin "4") (pinfunction "BISEN_4") (pintype "bidirectional"))
      (node (ref "IC7") (pin "PPAD") (pinfunction "V-_PPAD") (pintype "power_in"))
      (node (ref "IC8") (pin "1") (pinfunction "AISEN_1") (pintype "bidirectional"))
      (node (ref "IC8") (pin "11") (pinfunction "V-_11") (pintype "power_in"))
      (node (ref "IC8") (pin "4") (pinfunction "BISEN_4") (pintype "bidirectional"))
      (node (ref "IC8") (pin "PPAD") (pinfunction "V-_PPAD") (pintype "power_in"))
      (node (ref "IC9") (pin "1") (pinfunction "CLKIN_1") (pintype "bidirectional"))
      (node (ref "IC9") (pin "18") (pinfunction "V-_18") (pintype "power_in"))
      (node (ref "JP1") (pin "3") (pinfunction "3_3") (pintype "passive"))
      (node (ref "JP2") (pin "3") (pinfunction "3_3") (pintype "passive"))
      (node (ref "JP2") (pin "5") (pinfunction "5_5") (pintype "passive"))
      (node (ref "JP3") (pin "2") (pinfunction "2_2") (pintype "passive"))
      (node (ref "JP3") (pin "4") (pinfunction "4_4") (pintype "passive"))
      (node (ref "JP3") (pin "6") (pinfunction "6_6") (pintype "passive"))
      (node (ref "JP4") (pin "10") (pinfunction "DGND_10") (pintype "bidirectional"))
      (node (ref "JP4") (pin "19") (pinfunction "RESET_19") (pintype "bidirectional"))
      (node (ref "JP4") (pin "23") (pinfunction "AGND_23") (pintype "bidirectional"))
      (node (ref "OSC1") (pin "2") (pinfunction "GND_2") (pintype "bidirectional"))
      (node (ref "OSC2") (pin "2") (pinfunction "GND_2") (pintype "bidirectional"))
      (node (ref "OSC2") (pin "4") (pinfunction "GND_4") (pintype "bidirectional"))
      (node (ref "P2") (pin "1") (pinfunction "P_1") (pintype "passive"))
      (node (ref "R18") (pin "1") (pinfunction "1_1") (pintype "passive"))
      (node (ref "R2") (pin "1") (pinfunction "1_1") (pintype "passive"))
      (node (ref "R26") (pin "2") (pinfunction "2_2") (pintype "passive"))
      (node (ref "R27") (pin "2") (pinfunction "2_2") (pintype "passive"))
      (node (ref "R28") (pin "2") (pinfunction "2_2") (pintype "passive"))
      (node (ref "R6") (pin "2") (pinfunction "2_2") (pintype "passive"))
      (node (ref "R7") (pin "2") (pinfunction "2_2") (pintype "passive"))
    )
    (net (code "24") (name "GN_LED") (class "Default")
      (node (ref "IC4") (pin "28") (pinfunction "TDI/AN13/RB13_28") (pintype "bidirectional"))
      (node (ref "LED2") (pin "A") (pinfunction "A_A") (pintype "passive"))
    )
    (net (code "25") (name "IC3{slash}INT3{slash}RD10") (class "Default")
      (node (ref "IC4") (pin "44") (pinfunction "IC3/INT3/RD10_44") (pintype "bidirectional"))
      (node (ref "P16") (pin "1") (pinfunction "P_1") (pintype "passive"))
    )
    (net (code "26") (name "IMU_IRQ") (class "Default")
      (node (ref "IC4") (pin "42") (pinfunction "IC1/~{FLTA}/INT1/RD8_42") (pintype "bidirectional"))
      (node (ref "IC9") (pin "12") (pinfunction "INT_12") (pintype "bidirectional"))
    )
    (net (code "27") (name "LOWBATT_IRQ") (class "Default")
      (node (ref "IC1") (pin "2") (pinfunction "VOUT_2") (pintype "bidirectional"))
      (node (ref "IC4") (pin "43") (pinfunction "IC2/~{U1CTS}/~{FLTB}/INT2/RD9_43") (pintype "bidirectional"))
    )
    (net (code "28") (name "MOTOR_A_BEMF") (class "Default")
      (node (ref "C41") (pin "1") (pinfunction "1_1") (pintype "passive"))
      (node (ref "IC4") (pin "21") (pinfunction "~{U2CTS}/AN8/RB8_21") (pintype "bidirectional"))
      (node (ref "R29") (pin "2") (pinfunction "2_2") (pintype "passive"))
    )
    (net (code "29") (name "MOTOR_A_IN1") (class "Default")
      (node (ref "IC4") (pin "61") (pinfunction "PWM1H/RE1_61") (pintype "bidirectional"))
      (node (ref "IC7") (pin "14") (pinfunction "AIN1_14") (pintype "bidirectional"))
    )
    (net (code "30") (name "MOTOR_A_IN2") (class "Default")
      (node (ref "IC4") (pin "60") (pinfunction "PWM1L/RE0_60") (pintype "bidirectional"))
      (node (ref "IC7") (pin "13") (pinfunction "AIN2_13") (pintype "bidirectional"))
    )
    (net (code "31") (name "MOTOR_A_OUT1") (class "Default")
      (node (ref "C24") (pin "1") (pinfunction "1_1") (pintype "passive"))
      (node (ref "IC7") (pin "16") (pinfunction "AOUT1_16") (pintype "bidirectional"))
      (node (ref "P3") (pin "1") (pinfunction "P_1") (pintype "passive"))
      (node (ref "R9") (pin "1") (pinfunction "1_1") (pintype "passive"))
    )
    (net (code "32") (name "MOTOR_A_OUT2") (class "Default")
      (node (ref "C24") (pin "2") (pinfunction "2_2") (pintype "passive"))
      (node (ref "IC7") (pin "2") (pinfunction "AOUT2_2") (pintype "bidirectional"))
      (node (ref "P4") (pin "1") (pinfunction "P_1") (pintype "passive"))
      (node (ref "R10") (pin "1") (pinfunction "1_1") (pintype "passive"))
    )
    (net (code "33") (name "MOTOR_B_BEMF") (class "Default")
      (node (ref "C42") (pin "1") (pinfunction "1_1") (pintype "passive"))
      (node (ref "IC4") (pin "22") (pinfunction "AN9/RB9_22") (pintype "bidirectional"))
      (node (ref "R30") (pin "2") (pinfunction "2_2") (pintype "passive"))
    )
    (net (code "34") (name "MOTOR_B_IN1") (class "Default")
      (node (ref "IC4") (pin "63") (pinfunction "PWM2H/RE3_63") (pintype "bidirectional"))
      (node (ref "IC7") (pin "7") (pinfunction "BIN1_7") (pintype "bidirectional"))
    )
    (net (code "35") (name "MOTOR_B_IN2") (class "Default")
      (node (ref "IC4") (pin "62") (pinfunction "PWM2L/RE2_62") (pintype "bidirectional"))
      (node (ref "IC7") (pin "8") (pinfunction "BIN2_8") (pintype "bidirectional"))
    )
    (net (code "36") (name "MOTOR_B_OUT1") (class "Default")
      (node (ref "C25") (pin "1") (pinfunction "1_1") (pintype "passive"))
      (node (ref "IC7") (pin "5") (pinfunction "BOUT1_5") (pintype "bidirectional"))
      (node (ref "P5") (pin "1") (pinfunction "P_1") (pintype "passive"))
      (node (ref "R13") (pin "1") (pinfunction "1_1") (pintype "passive"))
    )
    (net (code "37") (name "MOTOR_B_OUT2") (class "Default")
      (node (ref "C25") (pin "2") (pinfunction "2_2") (pintype "passive"))
      (node (ref "IC7") (pin "3") (pinfunction "BOUT2_3") (pintype "bidirectional"))
      (node (ref "P6") (pin "1") (pinfunction "P_1") (pintype "passive"))
      (node (ref "R14") (pin "1") (pinfunction "1_1") (pintype "passive"))
    )
    (net (code "38") (name "MOTOR_C_BEMF") (class "Default")
      (node (ref "C43") (pin "1") (pinfunction "1_1") (pintype "passive"))
      (node (ref "IC4") (pin "23") (pinfunction "TMS/AN10/RB10_23") (pintype "bidirectional"))
      (node (ref "R31") (pin "2") (pinfunction "2_2") (pintype "passive"))
    )
    (net (code "39") (name "MOTOR_C_IN1") (class "Default")
      (node (ref "IC4") (pin "1") (pinfunction "PWM3H/RE5_1") (pintype "bidirectional"))
      (node (ref "IC8") (pin "14") (pinfunction "AIN1_14") (pintype "bidirectional"))
    )
    (net (code "40") (name "MOTOR_C_IN2") (class "Default")
      (node (ref "IC4") (pin "64") (pinfunction "PWM3L/RE4_64") (pintype "bidirectional"))
      (node (ref "IC8") (pin "13") (pinfunction "AIN2_13") (pintype "bidirectional"))
    )
    (net (code "41") (name "MOTOR_C_OUT1") (class "Default")
      (node (ref "C27") (pin "1") (pinfunction "1_1") (pintype "passive"))
      (node (ref "IC8") (pin "16") (pinfunction "AOUT1_16") (pintype "bidirectional"))
      (node (ref "P7") (pin "1") (pinfunction "P_1") (pintype "passive"))
      (node (ref "R19") (pin "1") (pinfunction "1_1") (pintype "passive"))
    )
    (net (code "42") (name "MOTOR_C_OUT2") (class "Default")
      (node (ref "C27") (pin "2") (pinfunction "2_2") (pintype "passive"))
      (node (ref "IC8") (pin "2") (pinfunction "AOUT2_2") (pintype "bidirectional"))
      (node (ref "P8") (pin "1") (pinfunction "P_1") (pintype "passive"))
      (node (ref "R20") (pin "1") (pinfunction "1_1") (pintype "passive"))
    )
    (net (code "43") (name "MOTOR_D_BEMF") (class "Default")
      (node (ref "C44") (pin "1") (pinfunction "1_1") (pintype "passive"))
      (node (ref "IC4") (pin "24") (pinfunction "TDO/AN11/RB11_24") (pintype "bidirectional"))
      (node (ref "R32") (pin "2") (pinfunction "2_2") (pintype "passive"))
    )
    (net (code "44") (name "MOTOR_D_IN1") (class "Default")
      (node (ref "IC4") (pin "3") (pinfunction "PWM4H/RE7_3") (pintype "bidirectional"))
      (node (ref "IC8") (pin "7") (pinfunction "BIN1_7") (pintype "bidirectional"))
    )
    (net (code "45") (name "MOTOR_D_IN2") (class "Default")
      (node (ref "IC4") (pin "2") (pinfunction "PWM4L/RE6_2") (pintype "bidirectional"))
      (node (ref "IC8") (pin "8") (pinfunction "BIN2_8") (pintype "bidirectional"))
    )
    (net (code "46") (name "MOTOR_D_OUT1") (class "Default")
      (node (ref "C28") (pin "1") (pinfunction "1_1") (pintype "passive"))
      (node (ref "IC8") (pin "5") (pinfunction "BOUT1_5") (pintype "bidirectional"))
      (node (ref "P9") (pin "1") (pinfunction "P_1") (pintype "passive"))
      (node (ref "R23") (pin "1") (pinfunction "1_1") (pintype "passive"))
    )
    (net (code "47") (name "MOTOR_D_OUT2") (class "Default")
      (node (ref "C28") (pin "2") (pinfunction "2_2") (pintype "passive"))
      (node (ref "IC8") (pin "3") (pinfunction "BOUT2_3") (pintype "bidirectional"))
      (node (ref "P10") (pin "1") (pinfunction "P_1") (pintype "passive"))
      (node (ref "R24") (pin "1") (pinfunction "1_1") (pintype "passive"))
    )
    (net (code "48") (name "Net-(ANT1-SIGNAL)") (class "Default")
      (node (ref "ANT1") (pin "A") (pinfunction "SIGNAL_A") (pintype "bidirectional"))
      (node (ref "B1") (pin "1") (pinfunction "UNBAL_1") (pintype "bidirectional"))
    )
    (net (code "49") (name "Net-(B1-BAL3)") (class "Default")
      (node (ref "B1") (pin "3") (pinfunction "BAL3_3") (pintype "bidirectional"))
      (node (ref "C17") (pin "1") (pinfunction "1_1") (pintype "passive"))
    )
    (net (code "50") (name "Net-(B1-BAL4)") (class "Default")
      (node (ref "B1") (pin "4") (pinfunction "BAL4_4") (pintype "bidirectional"))
      (node (ref "C16") (pin "2") (pinfunction "2_2") (pintype "passive"))
    )
    (net (code "51") (name "Net-(C22-Pad2)") (class "Default")
      (node (ref "C22") (pin "2") (pinfunction "2_2") (pintype "passive"))
      (node (ref "IC5") (pin "13") (pinfunction "V+_13") (pintype "power_in"))
      (node (ref "IC5") (pin "14") (pinfunction "V+_14") (pintype "power_in"))
    )
    (net (code "52") (name "Net-(IC4D-V+)") (class "Default")
      (node (ref "C10") (pin "1") (pinfunction "1_1") (pintype "passive"))
      (node (ref "IC4") (pin "19") (pinfunction "V+_19") (pintype "power_in"))
      (node (ref "L1") (pin "1") (pinfunction "1_1") (pintype "passive"))
    )
    (net (code "53") (name "Net-(IC4E-V+)") (class "Default")
      (node (ref "C15") (pin "1") (pinfunction "1_1") (pintype "passive"))
      (node (ref "IC4") (pin "56") (pinfunction "V+_56") (pintype "power_in"))
    )
    (net (code "54") (name "Net-(IC5A-V+)") (class "Default")
      (node (ref "C20") (pin "2") (pinfunction "2_2") (pintype "passive"))
      (node (ref "IC5") (pin "29") (pinfunction "V+_29") (pintype "power_in"))
    )
    (net (code "55") (name "Net-(IC5G-DIG2)") (class "Default")
      (node (ref "IC5") (pin "10") (pinfunction "DIG2_10") (pintype "bidirectional"))
      (node (ref "LED_TX") (pin "A") (pinfunction "A_A") (pintype "passive"))
    )
    (net (code "56") (name "Net-(IC5G-DIG3)") (class "Default")
      (node (ref "IC5") (pin "1") (pinfunction "DIG3_1") (pintype "bidirectional"))
      (node (ref "LED_RX") (pin "A") (pinfunction "A_A") (pintype "passive"))
    )
    (net (code "57") (name "Net-(IC5G-RFN)") (class "Default")
      (node (ref "C17") (pin "2") (pinfunction "2_2") (pintype "passive"))
      (node (ref "IC5") (pin "5") (pinfunction "RFN_5") (pintype "bidirectional"))
    )
    (net (code "58") (name "Net-(IC5G-RFP)") (class "Default")
      (node (ref "C16") (pin "1") (pinfunction "1_1") (pintype "passive"))
      (node (ref "IC5") (pin "4") (pinfunction "RFP_4") (pintype "bidirectional"))
    )
    (net (code "59") (name "Net-(IC5G-XTAL1)") (class "Default")
      (node (ref "C18") (pin "1") (pinfunction "1_1") (pintype "passive"))
      (node (ref "IC5") (pin "26") (pinfunction "XTAL1_26") (pintype "bidirectional"))
      (node (ref "OSC2") (pin "1") (pinfunction "IN/OUT_1") (pintype "bidirectional"))
    )
    (net (code "60") (name "Net-(IC5G-XTAL2)") (class "Default")
      (node (ref "C19") (pin "1") (pinfunction "1_1") (pintype "passive"))
      (node (ref "IC5") (pin "25") (pinfunction "XTAL2_25") (pintype "bidirectional"))
      (node (ref "OSC2") (pin "3") (pinfunction "OUT/IN_3") (pintype "bidirectional"))
    )
    (net (code "61") (name "Net-(IC6A-+IN)") (class "Default")
      (node (ref "IC6") (pin "3") (pinfunction "+IN_3") (pintype "input"))
      (node (ref "R10") (pin "2") (pinfunction "2_2") (pintype "passive"))
      (node (ref "R11") (pin "2") (pinfunction "2_2") (pintype "passive"))
    )
    (net (code "62") (name "Net-(IC6A--IN)") (class "Default")
      (node (ref "IC6") (pin "2") (pinfunction "-IN_2") (pintype "input"))
      (node (ref "R8") (pin "1") (pinfunction "1_1") (pintype "passive"))
      (node (ref "R9") (pin "2") (pinfunction "2_2") (pintype "passive"))
    )
    (net (code "63") (name "Net-(IC6A-OUT)") (class "Default")
      (node (ref "IC6") (pin "1") (pinfunction "OUT_1") (pintype "output"))
      (node (ref "R29") (pin "1") (pinfunction "1_1") (pintype "passive"))
      (node (ref "R8") (pin "2") (pinfunction "2_2") (pintype "passive"))
    )
    (net (code "64") (name "Net-(IC6B-+IN)") (class "Default")
      (node (ref "IC6") (pin "5") (pinfunction "+IN_5") (pintype "input"))
      (node (ref "R14") (pin "2") (pinfunction "2_2") (pintype "passive"))
      (node (ref "R15") (pin "2") (pinfunction "2_2") (pintype "passive"))
    )
    (net (code "65") (name "Net-(IC6B--IN)") (class "Default")
      (node (ref "IC6") (pin "6") (pinfunction "-IN_6") (pintype "input"))
      (node (ref "R12") (pin "1") (pinfunction "1_1") (pintype "passive"))
      (node (ref "R13") (pin "2") (pinfunction "2_2") (pintype "passive"))
    )
    (net (code "66") (name "Net-(IC6B-OUT)") (class "Default")
      (node (ref "IC6") (pin "7") (pinfunction "OUT_7") (pintype "output"))
      (node (ref "R12") (pin "2") (pinfunction "2_2") (pintype "passive"))
      (node (ref "R30") (pin "1") (pinfunction "1_1") (pintype "passive"))
    )
    (net (code "67") (name "Net-(IC6C-+IN)") (class "Default")
      (node (ref "IC6") (pin "12") (pinfunction "+IN_12") (pintype "input"))
      (node (ref "R20") (pin "2") (pinfunction "2_2") (pintype "passive"))
      (node (ref "R21") (pin "2") (pinfunction "2_2") (pintype "passive"))
    )
    (net (code "68") (name "Net-(IC6C--IN)") (class "Default")
      (node (ref "IC6") (pin "11") (pinfunction "-IN_11") (pintype "input"))
      (node (ref "R17") (pin "1") (pinfunction "1_1") (pintype "passive"))
      (node (ref "R19") (pin "2") (pinfunction "2_2") (pintype "passive"))
    )
    (net (code "69") (name "Net-(IC6C-OUT)") (class "Default")
      (node (ref "IC6") (pin "10") (pinfunction "OUT_10") (pintype "output"))
      (node (ref "R17") (pin "2") (pinfunction "2_2") (pintype "passive"))
      (node (ref "R31") (pin "1") (pinfunction "1_1") (pintype "passive"))
    )
    (net (code "70") (name "Net-(IC6D-+IN)") (class "Default")
      (node (ref "IC6") (pin "14") (pinfunction "+IN_14") (pintype "input"))
      (node (ref "R24") (pin "2") (pinfunction "2_2") (pintype "passive"))
      (node (ref "R25") (pin "2") (pinfunction "2_2") (pintype "passive"))
    )
    (net (code "71") (name "Net-(IC6D--IN)") (class "Default")
      (node (ref "IC6") (pin "15") (pinfunction "-IN_15") (pintype "input"))
      (node (ref "R22") (pin "1") (pinfunction "1_1") (pintype "passive"))
      (node (ref "R23") (pin "2") (pinfunction "2_2") (pintype "passive"))
    )
    (net (code "72") (name "Net-(IC6D-OUT)") (class "Default")
      (node (ref "IC6") (pin "16") (pinfunction "OUT_16") (pintype "output"))
      (node (ref "R22") (pin "2") (pinfunction "2_2") (pintype "passive"))
      (node (ref "R32") (pin "1") (pinfunction "1_1") (pintype "passive"))
    )
    (net (code "73") (name "Net-(IC7A-V+)") (class "Default")
      (node (ref "C31") (pin "2") (pinfunction "2_2") (pintype "passive"))
      (node (ref "IC7") (pin "9") (pinfunction "V+_9") (pintype "power_in"))
    )
    (net (code "74") (name "Net-(IC7B-V-)") (class "Default")
      (node (ref "C32") (pin "1") (pinfunction "1_1") (pintype "passive"))
      (node (ref "IC7") (pin "12") (pinfunction "V-_12") (pintype "power_in"))
    )
    (net (code "75") (name "Net-(IC8A-V+)") (class "Default")
      (node (ref "C34") (pin "2") (pinfunction "2_2") (pintype "passive"))
      (node (ref "IC8") (pin "9") (pinfunction "V+_9") (pintype "power_in"))
    )
    (net (code "76") (name "Net-(IC8B-V-)") (class "Default")
      (node (ref "C35") (pin "1") (pinfunction "1_1") (pintype "passive"))
      (node (ref "IC8") (pin "12") (pinfunction "V-_12") (pintype "power_in"))
    )
    (net (code "77") (name "Net-(IC9A-V-)") (class "Default")
      (node (ref "C38") (pin "2") (pinfunction "2_2") (pintype "passive"))
      (node (ref "IC9") (pin "20") (pinfunction "V-_20") (pintype "power_in"))
    )
    (net (code "78") (name "Net-(IC9B-V-)") (class "Default")
      (node (ref "C39") (pin "2") (pinfunction "2_2") (pintype "passive"))
      (node (ref "IC9") (pin "10") (pinfunction "V-_10") (pintype "power_in"))
    )
    (net (code "79") (name "Net-(LED1-PadC)") (class "Default")
      (node (ref "LED1") (pin "C") (pinfunction "C_C") (pintype "passive"))
      (node (ref "R26") (pin "1") (pinfunction "1_1") (pintype "passive"))
    )
    (net (code "80") (name "Net-(LED2-PadC)") (class "Default")
      (node (ref "LED2") (pin "C") (pinfunction "C_C") (pintype "passive"))
      (node (ref "R27") (pin "1") (pinfunction "1_1") (pintype "passive"))
    )
    (net (code "81") (name "Net-(LED3-PadC)") (class "Default")
      (node (ref "LED3") (pin "C") (pinfunction "C_C") (pintype "passive"))
      (node (ref "R28") (pin "1") (pinfunction "1_1") (pintype "passive"))
    )
    (net (code "82") (name "Net-(LED_RX-PadC)") (class "Default")
      (node (ref "LED_RX") (pin "C") (pinfunction "C_C") (pintype "passive"))
      (node (ref "R7") (pin "1") (pinfunction "1_1") (pintype "passive"))
    )
    (net (code "83") (name "Net-(LED_TX-PadC)") (class "Default")
      (node (ref "LED_TX") (pin "C") (pinfunction "C_C") (pintype "passive"))
      (node (ref "R6") (pin "1") (pinfunction "1_1") (pintype "passive"))
    )
    (net (code "84") (name "PGC") (class "Default")
      (node (ref "IC4") (pin "17") (pinfunction "PGEC1/AN6/OCFA/RB6_17") (pintype "bidirectional"))
      (node (ref "JP1") (pin "5") (pinfunction "5_5") (pintype "passive"))
    )
    (net (code "85") (name "PGD") (class "Default")
      (node (ref "IC4") (pin "18") (pinfunction "PGED1/AN7/RB7_18") (pintype "bidirectional"))
      (node (ref "JP1") (pin "4") (pinfunction "4_4") (pintype "passive"))
    )
    (net (code "86") (name "RADIO_IRQ") (class "Default")
      (node (ref "IC4") (pin "45") (pinfunction "IC4/INT4/RD11_45") (pintype "bidirectional"))
      (node (ref "IC5") (pin "24") (pinfunction "IRQ_24") (pintype "bidirectional"))
    )
    (net (code "87") (name "RADIO_SLP_TR") (class "Default")
      (node (ref "IC4") (pin "30") (pinfunction "AN15/OCFB/CN12/RB15_30") (pintype "bidirectional"))
      (node (ref "IC5") (pin "11") (pinfunction "SLP_TR_11") (pintype "bidirectional"))
    )
    (net (code "88") (name "RD_LED") (class "Default")
      (node (ref "IC4") (pin "27") (pinfunction "TCK/AN12/RB12_27") (pintype "bidirectional"))
      (node (ref "LED3") (pin "A") (pinfunction "A_A") (pintype "passive"))
    )
    (net (code "89") (name "SCK1") (class "Default")
      (node (ref "IC4") (pin "35") (pinfunction "~{U1RTS}/SCK1/INT0/RF6_35") (pintype "bidirectional"))
      (node (ref "IC5") (pin "19") (pinfunction "SCLK_19") (pintype "bidirectional"))
    )
    (net (code "90") (name "SCK2") (class "Default")
      (node (ref "IC10") (pin "2") (pinfunction "SCK_2") (pintype "bidirectional"))
      (node (ref "IC4") (pin "4") (pinfunction "SCK2/CN8/RG6_4") (pintype "bidirectional"))
      (node (ref "IC9") (pin "23") (pinfunction "SCL/SCLK_23") (pintype "bidirectional"))
    )
    (net (code "91") (name "SCL1") (class "Default")
      (node (ref "IC4") (pin "36") (pinfunction "SCL1/RG2_36") (pintype "bidirectional"))
      (node (ref "JP3") (pin "3") (pinfunction "3_3") (pintype "passive"))
      (node (ref "JP4") (pin "20") (pinfunction "SIO_C_20") (pintype "bidirectional"))
      (node (ref "R4") (pin "1") (pinfunction "1_1") (pintype "passive"))
    )
    (net (code "92") (name "SDA1") (class "Default")
      (node (ref "IC4") (pin "37") (pinfunction "SDA1/RG3_37") (pintype "bidirectional"))
      (node (ref "JP3") (pin "5") (pinfunction "5_5") (pintype "passive"))
      (node (ref "JP4") (pin "22") (pinfunction "SIO_D_22") (pintype "bidirectional"))
      (node (ref "R5") (pin "1") (pinfunction "1_1") (pintype "passive"))
    )
    (net (code "93") (name "SDI1") (class "Default")
      (node (ref "IC4") (pin "34") (pinfunction "U1RX/SDI1/RF2_34") (pintype "bidirectional"))
      (node (ref "IC5") (pin "20") (pinfunction "MISO_20") (pintype "bidirectional"))
    )
    (net (code "94") (name "SDI2") (class "Default")
      (node (ref "IC10") (pin "8") (pinfunction "SO_8") (pintype "bidirectional"))
      (node (ref "IC4") (pin "5") (pinfunction "SDI2/CN9/RG7_5") (pintype "bidirectional"))
      (node (ref "IC9") (pin "9") (pinfunction "AD0/SDO_9") (pintype "bidirectional"))
    )
    (net (code "95") (name "SDO1") (class "Default")
      (node (ref "IC4") (pin "33") (pinfunction "U1TX/SDO1/RF3_33") (pintype "bidirectional"))
      (node (ref "IC5") (pin "22") (pinfunction "MOSI_22") (pintype "bidirectional"))
    )
    (net (code "96") (name "SDO2") (class "Default")
      (node (ref "IC10") (pin "1") (pinfunction "SI_1") (pintype "bidirectional"))
      (node (ref "IC4") (pin "6") (pinfunction "SDO2/CN10/RG8_6") (pintype "bidirectional"))
      (node (ref "IC9") (pin "24") (pinfunction "SDA/SDI_24") (pintype "bidirectional"))
    )
    (net (code "97") (name "U2RX") (class "Default")
      (node (ref "IC4") (pin "31") (pinfunction "U2RX/SDA2/CN17/RF4_31") (pintype "bidirectional"))
      (node (ref "JP2") (pin "6") (pinfunction "6_6") (pintype "passive"))
    )
    (net (code "98") (name "U2TX") (class "Default")
      (node (ref "IC4") (pin "32") (pinfunction "U2TX/SCL2/CN18/RF5_32") (pintype "bidirectional"))
      (node (ref "JP2") (pin "4") (pinfunction "4_4") (pintype "passive"))
    )
    (net (code "99") (name "V_BATT") (class "Default")
      (node (ref "C3") (pin "1") (pinfunction "1_1") (pintype "passive"))
      (node (ref "C30") (pin "1") (pinfunction "1_1") (pintype "passive"))
      (node (ref "C31") (pin "1") (pinfunction "1_1") (pintype "passive"))
      (node (ref "C33") (pin "1") (pinfunction "1_1") (pintype "passive"))
      (node (ref "C34") (pin "1") (pinfunction "1_1") (pintype "passive"))
      (node (ref "C4") (pin "2") (pinfunction "2_2") (pintype "passive"))
      (node (ref "C5") (pin "2") (pinfunction "2_2") (pintype "passive"))
      (node (ref "IC1") (pin "3") (pinfunction "VIN_3") (pintype "bidirectional"))
      (node (ref "IC2") (pin "1") (pinfunction "VIN_1") (pintype "bidirectional"))
      (node (ref "IC2") (pin "3") (pinfunction "EN_3.0V_3") (pintype "bidirectional"))
      (node (ref "IC2") (pin "4") (pinfunction "EN_3.3V_4") (pintype "bidirectional"))
      (node (ref "IC3") (pin "1") (pinfunction "VIN_1") (pintype "bidirectional"))
      (node (ref "IC3") (pin "3") (pinfunction "EN_1.8V_3") (pintype "bidirectional"))
      (node (ref "IC3") (pin "4") (pinfunction "EN_2.5V_4") (pintype "bidirectional"))
      (node (ref "IC7") (pin "10") (pinfunction "V+_10") (pintype "power_in"))
      (node (ref "IC7") (pin "15") (pinfunction "~{SLEEP}_15") (pintype "bidirectional"))
      (node (ref "IC8") (pin "10") (pinfunction "V+_10") (pintype "power_in"))
      (node (ref "IC8") (pin "15") (pinfunction "~{SLEEP}_15") (pintype "bidirectional"))
      (node (ref "JP2") (pin "1") (pinfunction "1_1") (pintype "passive"))
      (node (ref "JP2") (pin "2") (pinfunction "2_2") (pintype "passive"))
      (node (ref "P1") (pin "1") (pinfunction "P_1") (pintype "passive"))
      (node (ref "R1") (pin "2") (pinfunction "2_2") (pintype "passive"))
    )
    (net (code "100") (name "V_REF") (class "Default")
      (node (ref "C26") (pin "1") (pinfunction "1_1") (pintype "passive"))
      (node (ref "R11") (pin "1") (pinfunction "1_1") (pintype "passive"))
      (node (ref "R15") (pin "1") (pinfunction "1_1") (pintype "passive"))
      (node (ref "R16") (pin "1") (pinfunction "1_1") (pintype "passive"))
      (node (ref "R18") (pin "2") (pinfunction "2_2") (pintype "passive"))
      (node (ref "R21") (pin "1") (pinfunction "1_1") (pintype "passive"))
      (node (ref "R25") (pin "1") (pinfunction "1_1") (pintype "passive"))
    )
    (net (code "101") (name "YW_LED") (class "Default")
      (node (ref "IC4") (pin "29") (pinfunction "~{U2RTS}/AN14/RB14_29") (pintype "bidirectional"))
      (node (ref "LED1") (pin "A") (pinfunction "A_A") (pintype "passive"))
    )
    (net (code "102") (name "unconnected-(B1-NC-Pad6)") (class "Default")
      (node (ref "B1") (pin "6") (pinfunction "NC_6") (pintype "bidirectional"))
    )
    (net (code "103") (name "unconnected-(IC5G-CLKM-Pad17)") (class "Default")
      (node (ref "IC5") (pin "17") (pinfunction "CLKM_17") (pintype "bidirectional"))
    )
    (net (code "104") (name "unconnected-(IC5G-DIG1-Pad9)") (class "Default")
      (node (ref "IC5") (pin "9") (pinfunction "DIG1_9") (pintype "bidirectional"))
    )
    (net (code "105") (name "unconnected-(IC5G-DIG4-Pad2)") (class "Default")
      (node (ref "IC5") (pin "2") (pinfunction "DIG4_2") (pintype "bidirectional"))
    )
    (net (code "106") (name "unconnected-(IC7D-~{FAULT}-Pad6)") (class "Default")
      (node (ref "IC7") (pin "6") (pinfunction "~{FAULT}_6") (pintype "bidirectional"))
    )
    (net (code "107") (name "unconnected-(IC8D-~{FAULT}-Pad6)") (class "Default")
      (node (ref "IC8") (pin "6") (pinfunction "~{FAULT}_6") (pintype "bidirectional"))
    )
    (net (code "108") (name "unconnected-(IC9D-AUX_CL-Pad7)") (class "Default")
      (node (ref "IC9") (pin "7") (pinfunction "AUX_CL_7") (pintype "bidirectional"))
    )
    (net (code "109") (name "unconnected-(IC9D-AUX_DA-Pad6)") (class "Default")
      (node (ref "IC9") (pin "6") (pinfunction "AUX_DA_6") (pintype "bidirectional"))
    )
    (net (code "110") (name "unconnected-(IC9D-CLKOUT-Pad22)") (class "Default")
      (node (ref "IC9") (pin "22") (pinfunction "CLKOUT_22") (pintype "bidirectional"))
    )
    (net (code "111") (name "unconnected-(JP1-Pad6)") (class "Default")
      (node (ref "JP1") (pin "6") (pinfunction "6_6") (pintype "passive"))
    )
    (net (code "112") (name "unconnected-(JP4-NC-Pad1)") (class "Default")
      (node (ref "JP4") (pin "1") (pinfunction "NC_1") (pintype "bidirectional"))
    )
    (net (code "113") (name "unconnected-(JP4-NC-Pad2)") (class "Default")
      (node (ref "JP4") (pin "2") (pinfunction "NC_2") (pintype "bidirectional"))
    )
    (net (code "114") (name "unconnected-(JP4-NC-Pad24)") (class "Default")
      (node (ref "JP4") (pin "24") (pinfunction "NC_24") (pintype "bidirectional"))
    )
    (net (code "115") (name "unconnected-(OSC1-EN-Pad1)") (class "Default")
      (node (ref "OSC1") (pin "1") (pinfunction "EN_1") (pintype "bidirectional"))
    )
    (net (code "116") (name "~{RESET}") (class "Default")
      (node (ref "IC10") (pin "3") (pinfunction "~{RESET}_3") (pintype "bidirectional"))
      (node (ref "IC4") (pin "7") (pinfunction "~{MCLR}_7") (pintype "input"))
      (node (ref "IC5") (pin "8") (pinfunction "~{RST}_8") (pintype "bidirectional"))
      (node (ref "JP1") (pin "1") (pinfunction "1_1") (pintype "passive"))
      (node (ref "R3") (pin "1") (pinfunction "1_1") (pintype "passive"))
    )
    (net (code "117") (name "~{SS1}") (class "Default")
      (node (ref "IC4") (pin "14") (pinfunction "AN2/~{SS1}/CN4/RB2_14") (pintype "bidirectional"))
      (node (ref "IC5") (pin "23") (pinfunction "~{SEL}_23") (pintype "bidirectional"))
    )
    (net (code "118") (name "~{SS2_1}") (class "Default")
      (node (ref "IC10") (pin "4") (pinfunction "~{CS}_4") (pintype "bidirectional"))
      (node (ref "IC4") (pin "8") (pinfunction "~{SS2}/CN11/RG9_8") (pintype "bidirectional"))
    )
    (net (code "119") (name "~{SS2_2}") (class "Default")
      (node (ref "IC4") (pin "40") (pinfunction "OSC2/CLKO/RC15_40") (pintype "bidirectional"))
      (node (ref "IC9") (pin "8") (pinfunction "~{CS}_8") (pintype "bidirectional"))
    )
  )
)
